# 32KRAM.net
KiCad netlist of a schematic drawn in EAGLE
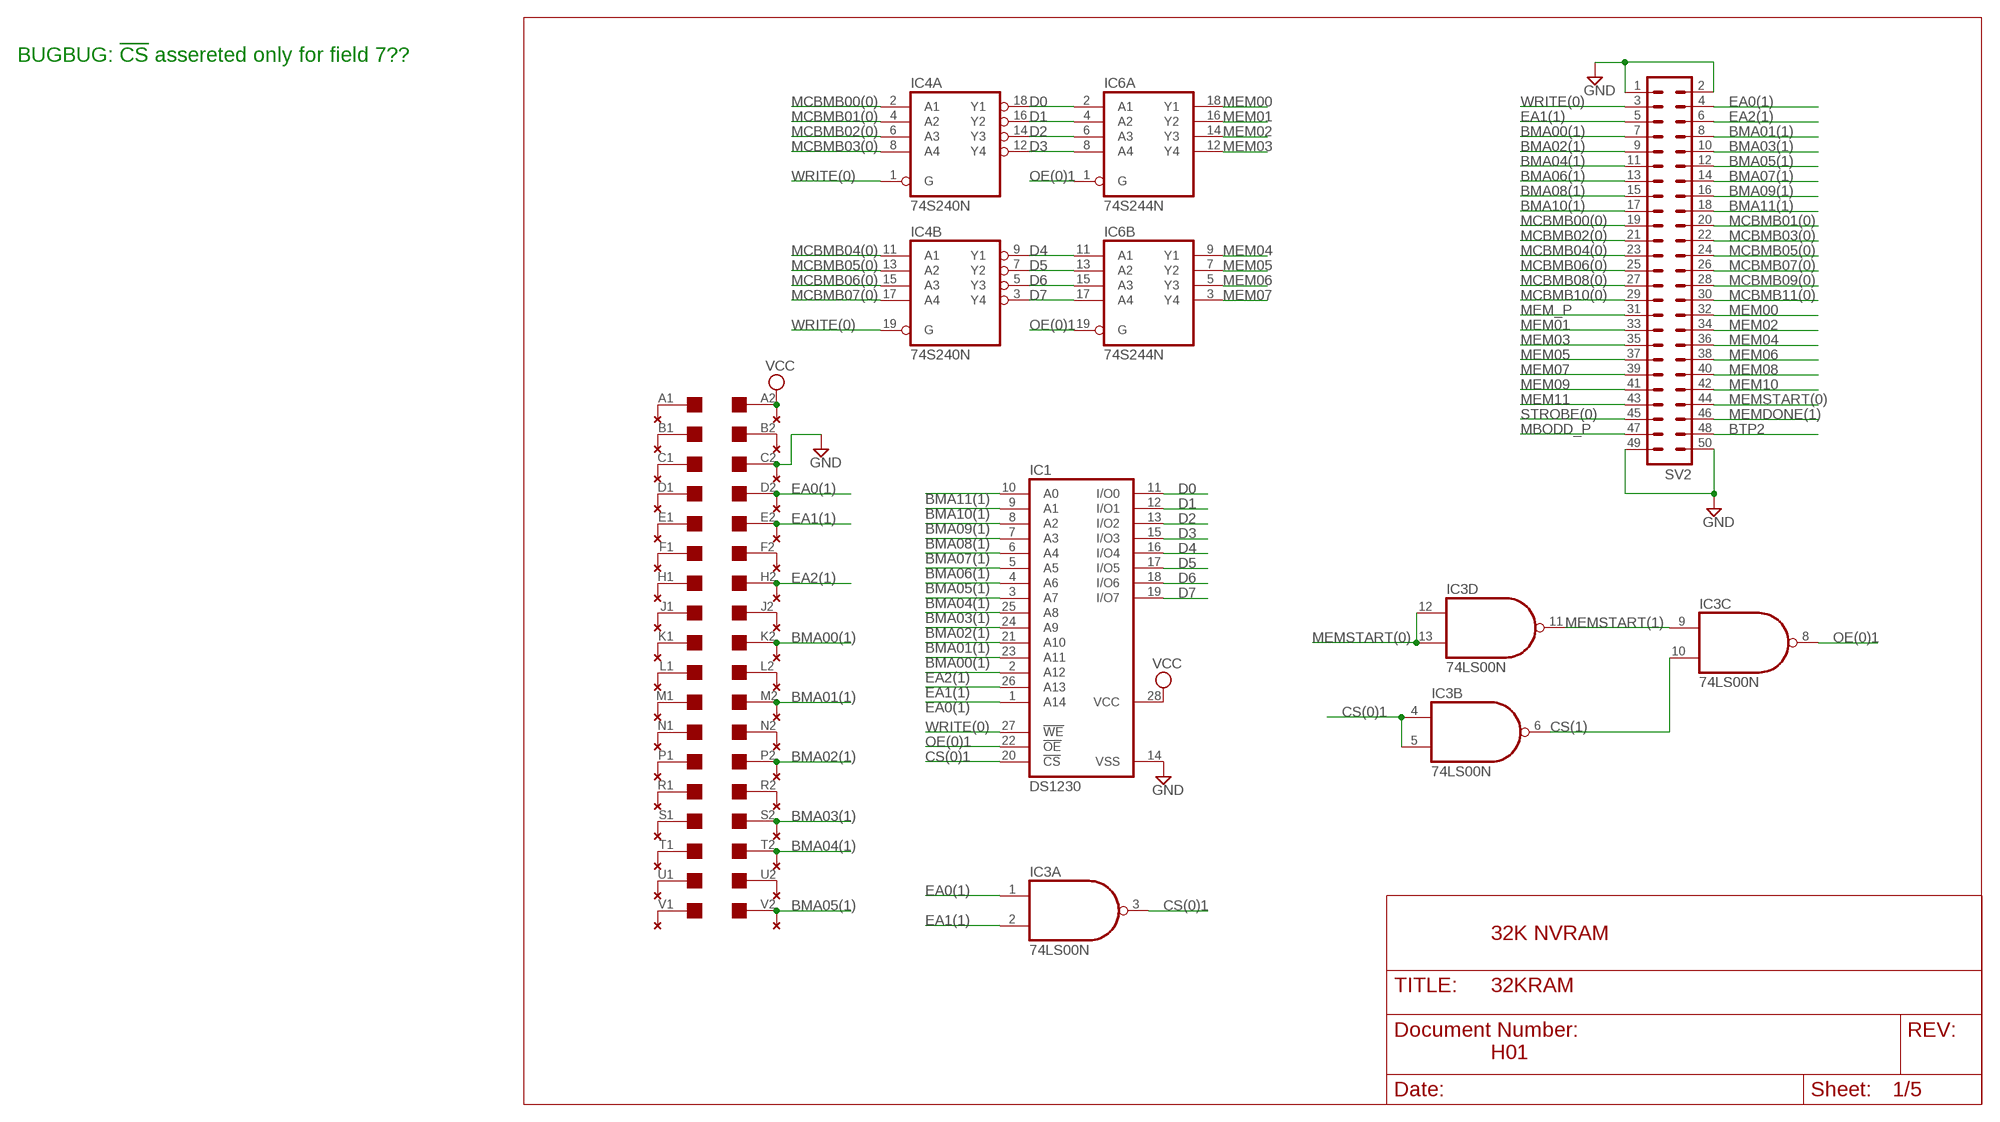
[diagram p0: schematic, sheet 1]
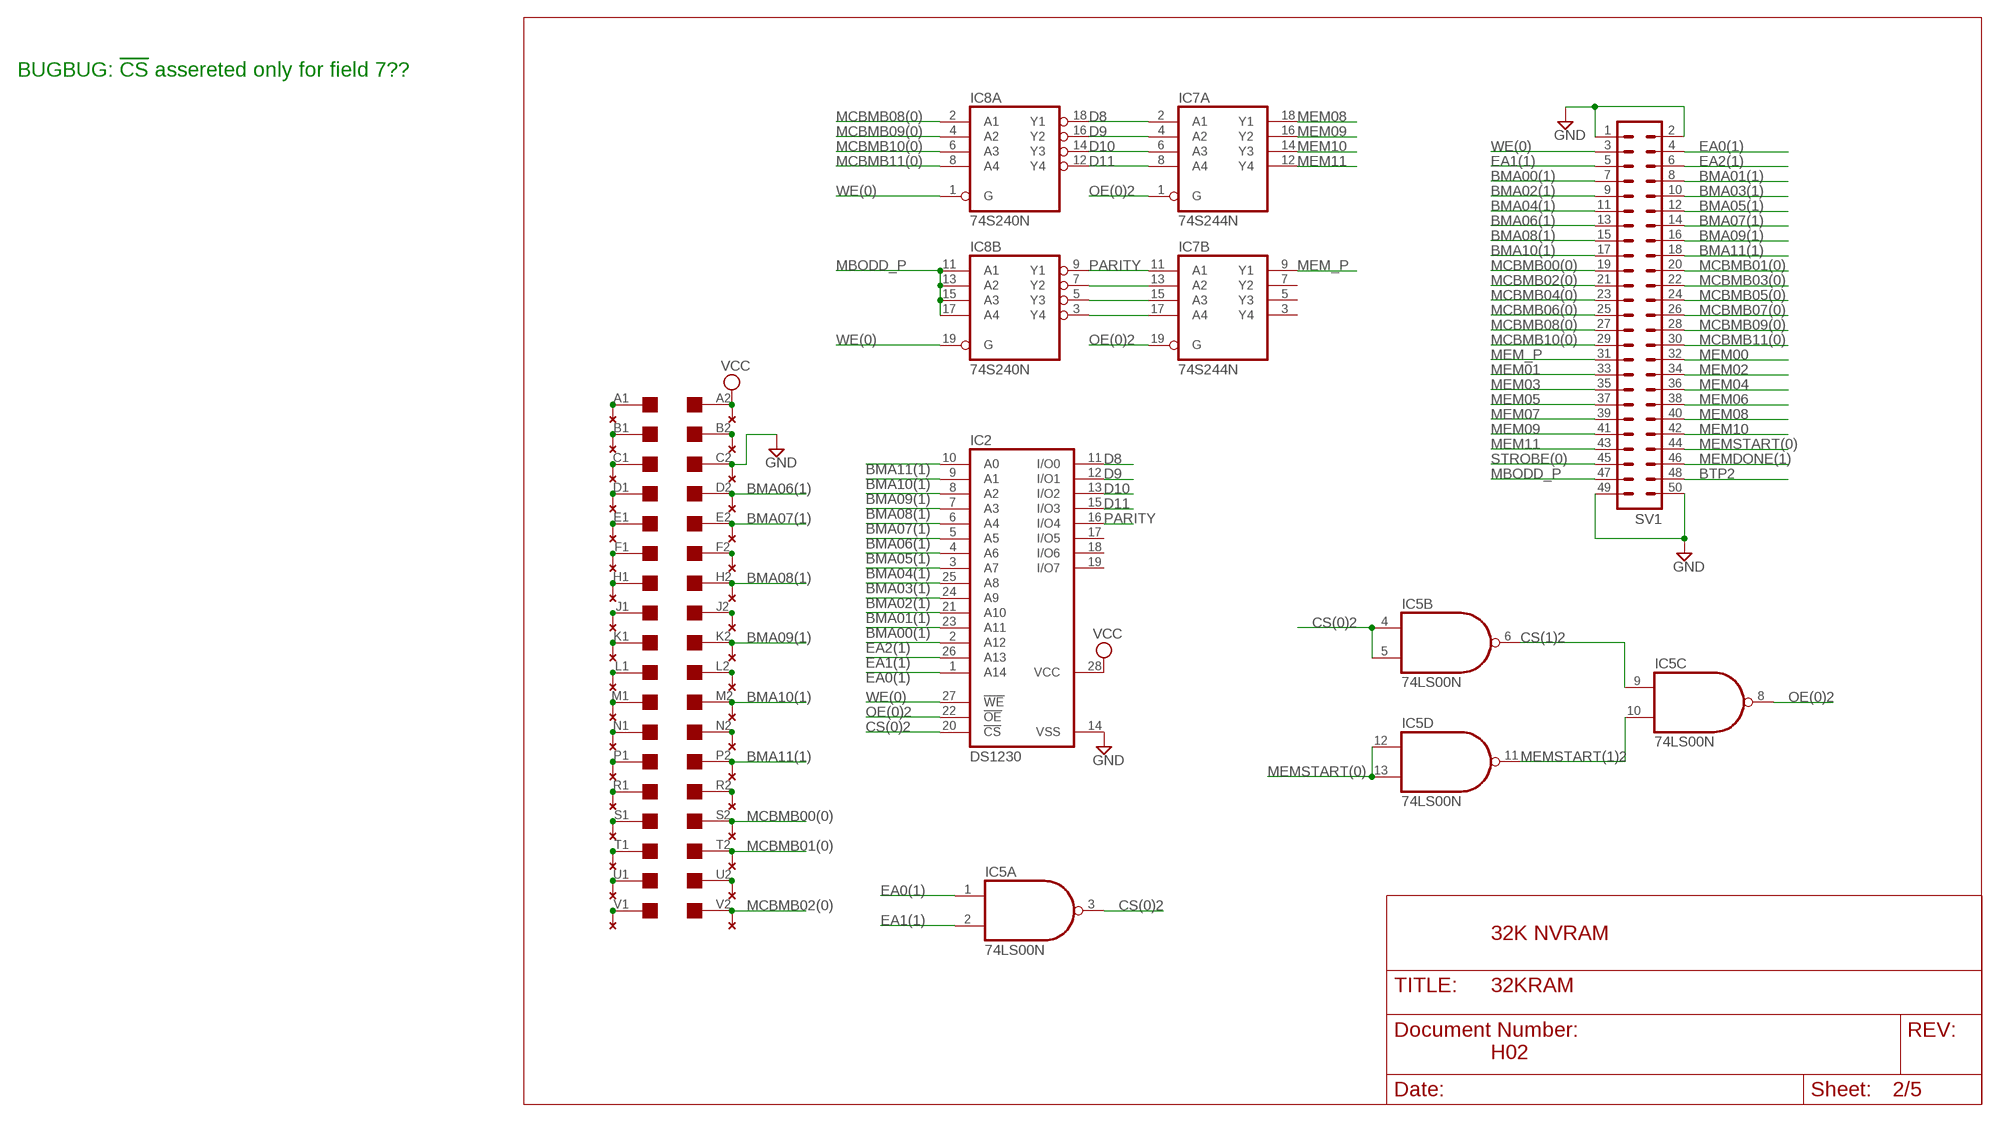
[diagram p1: schematic, sheet 2]
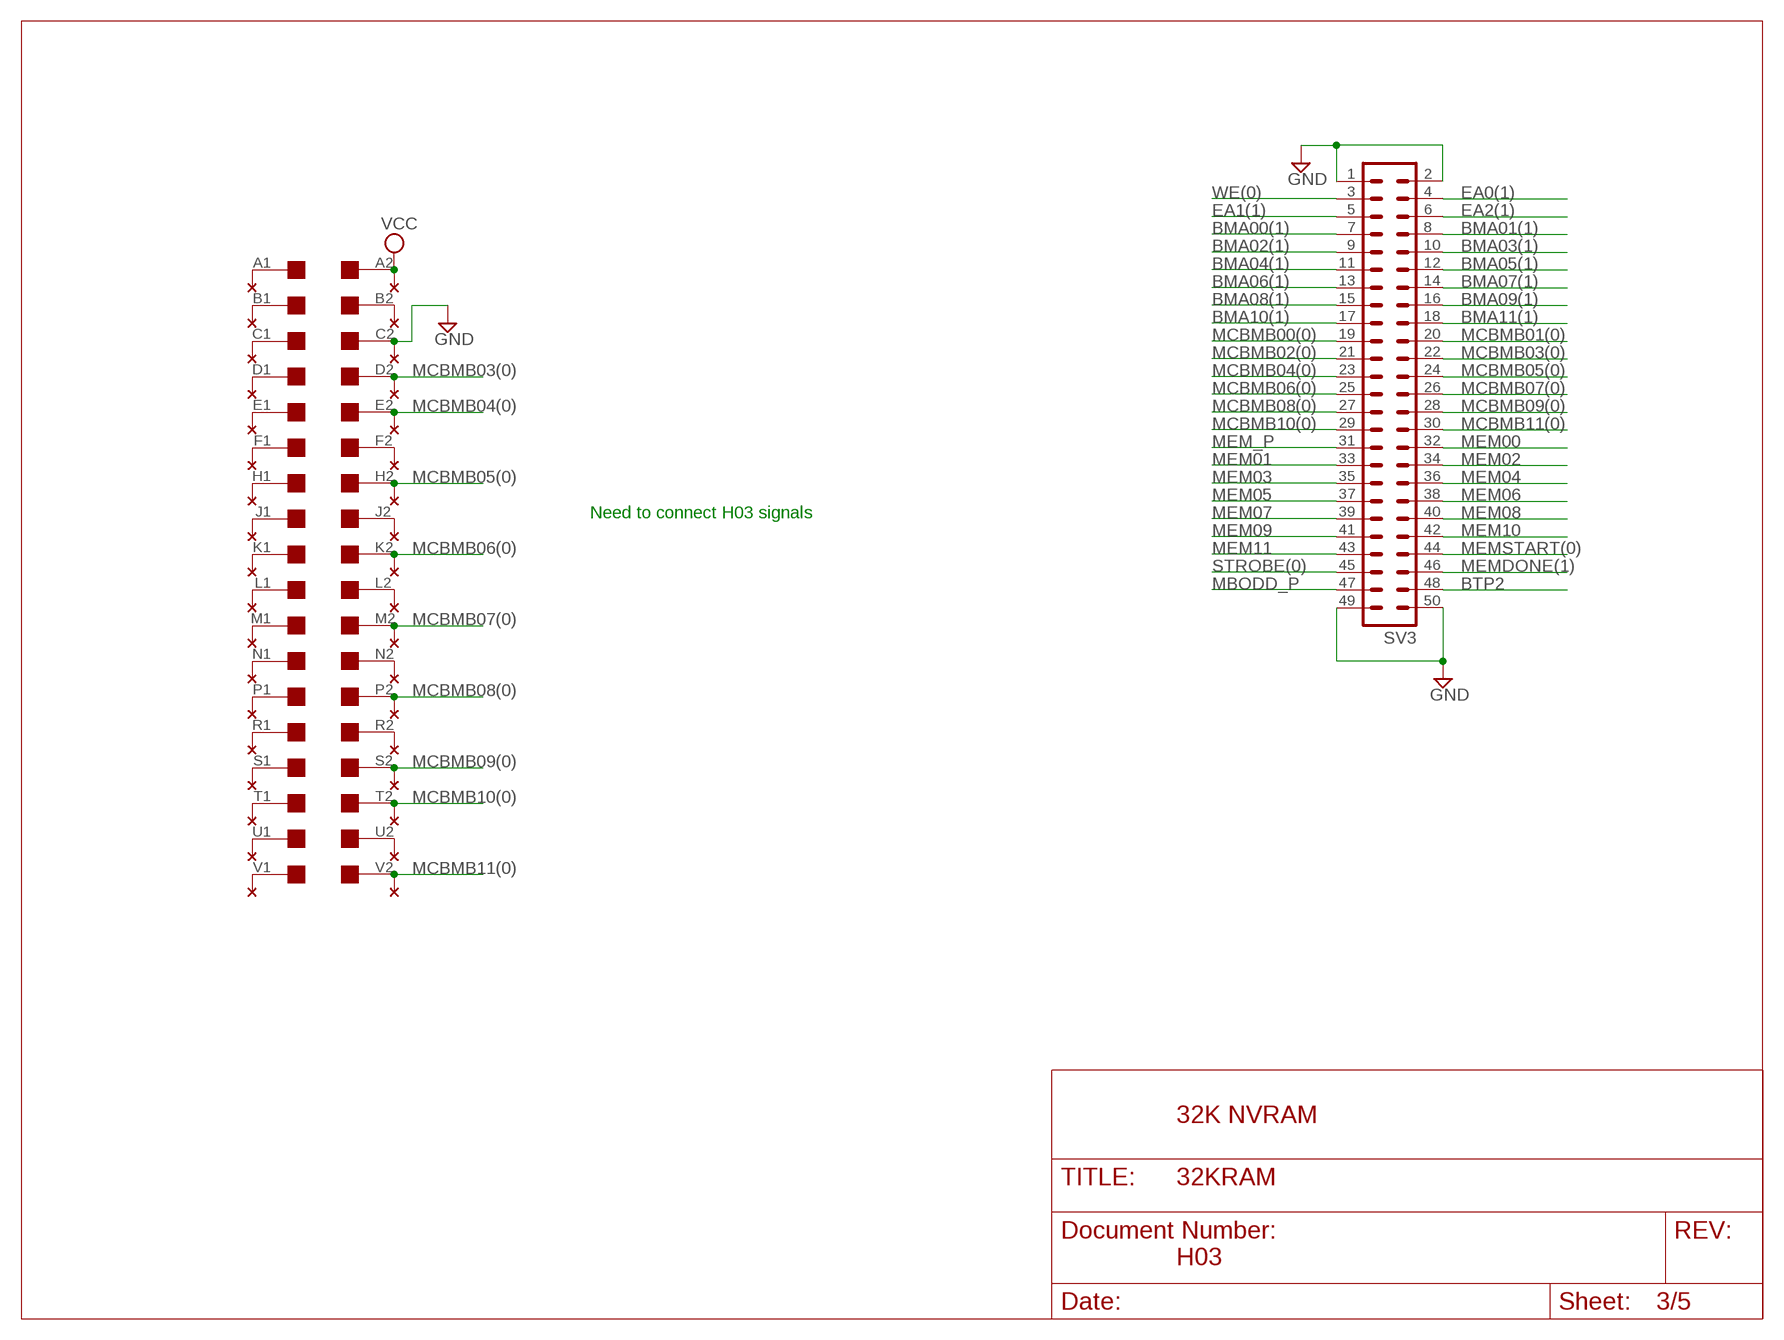
[diagram p2: schematic, sheet 3]
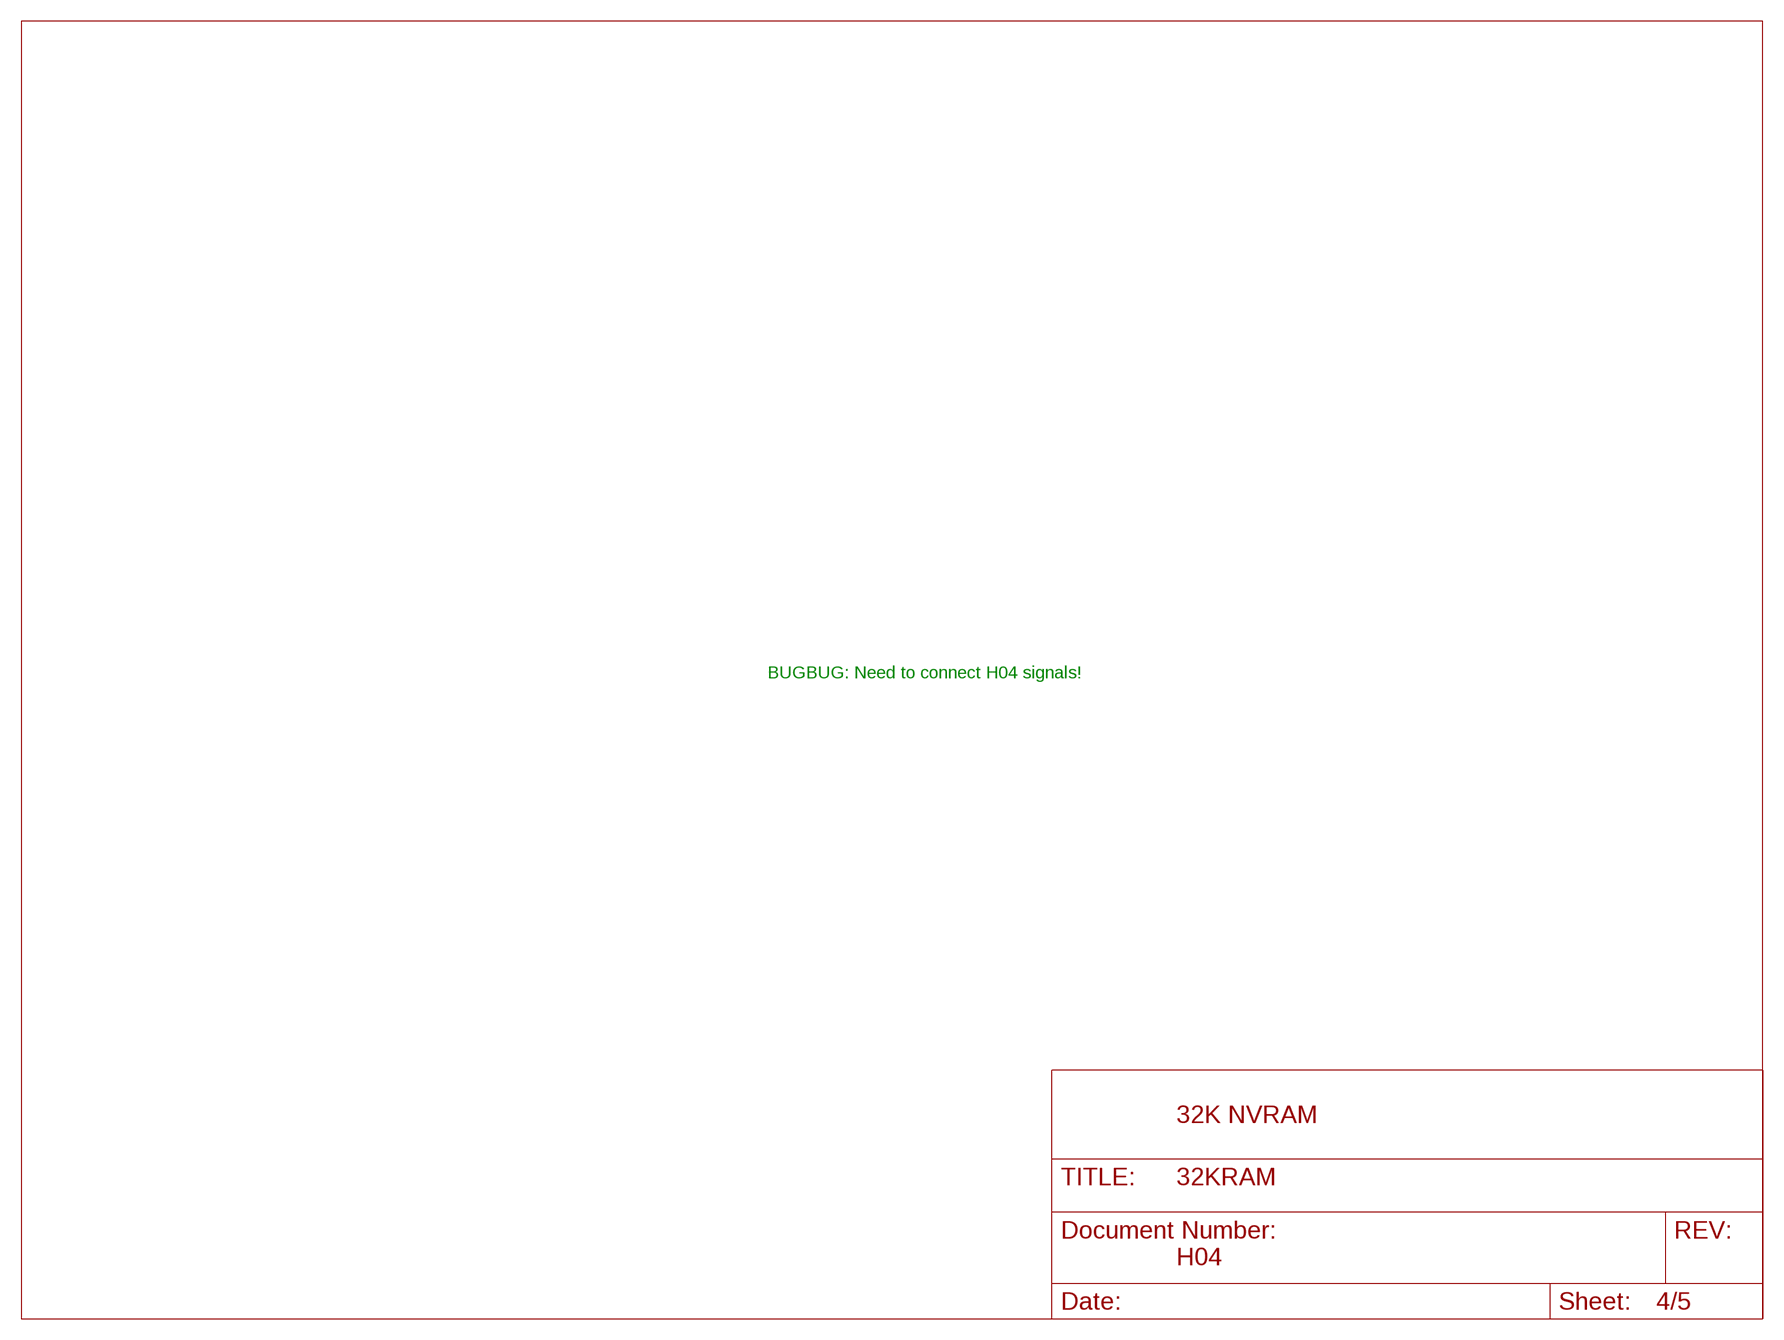
[diagram p3: schematic, sheet 4]
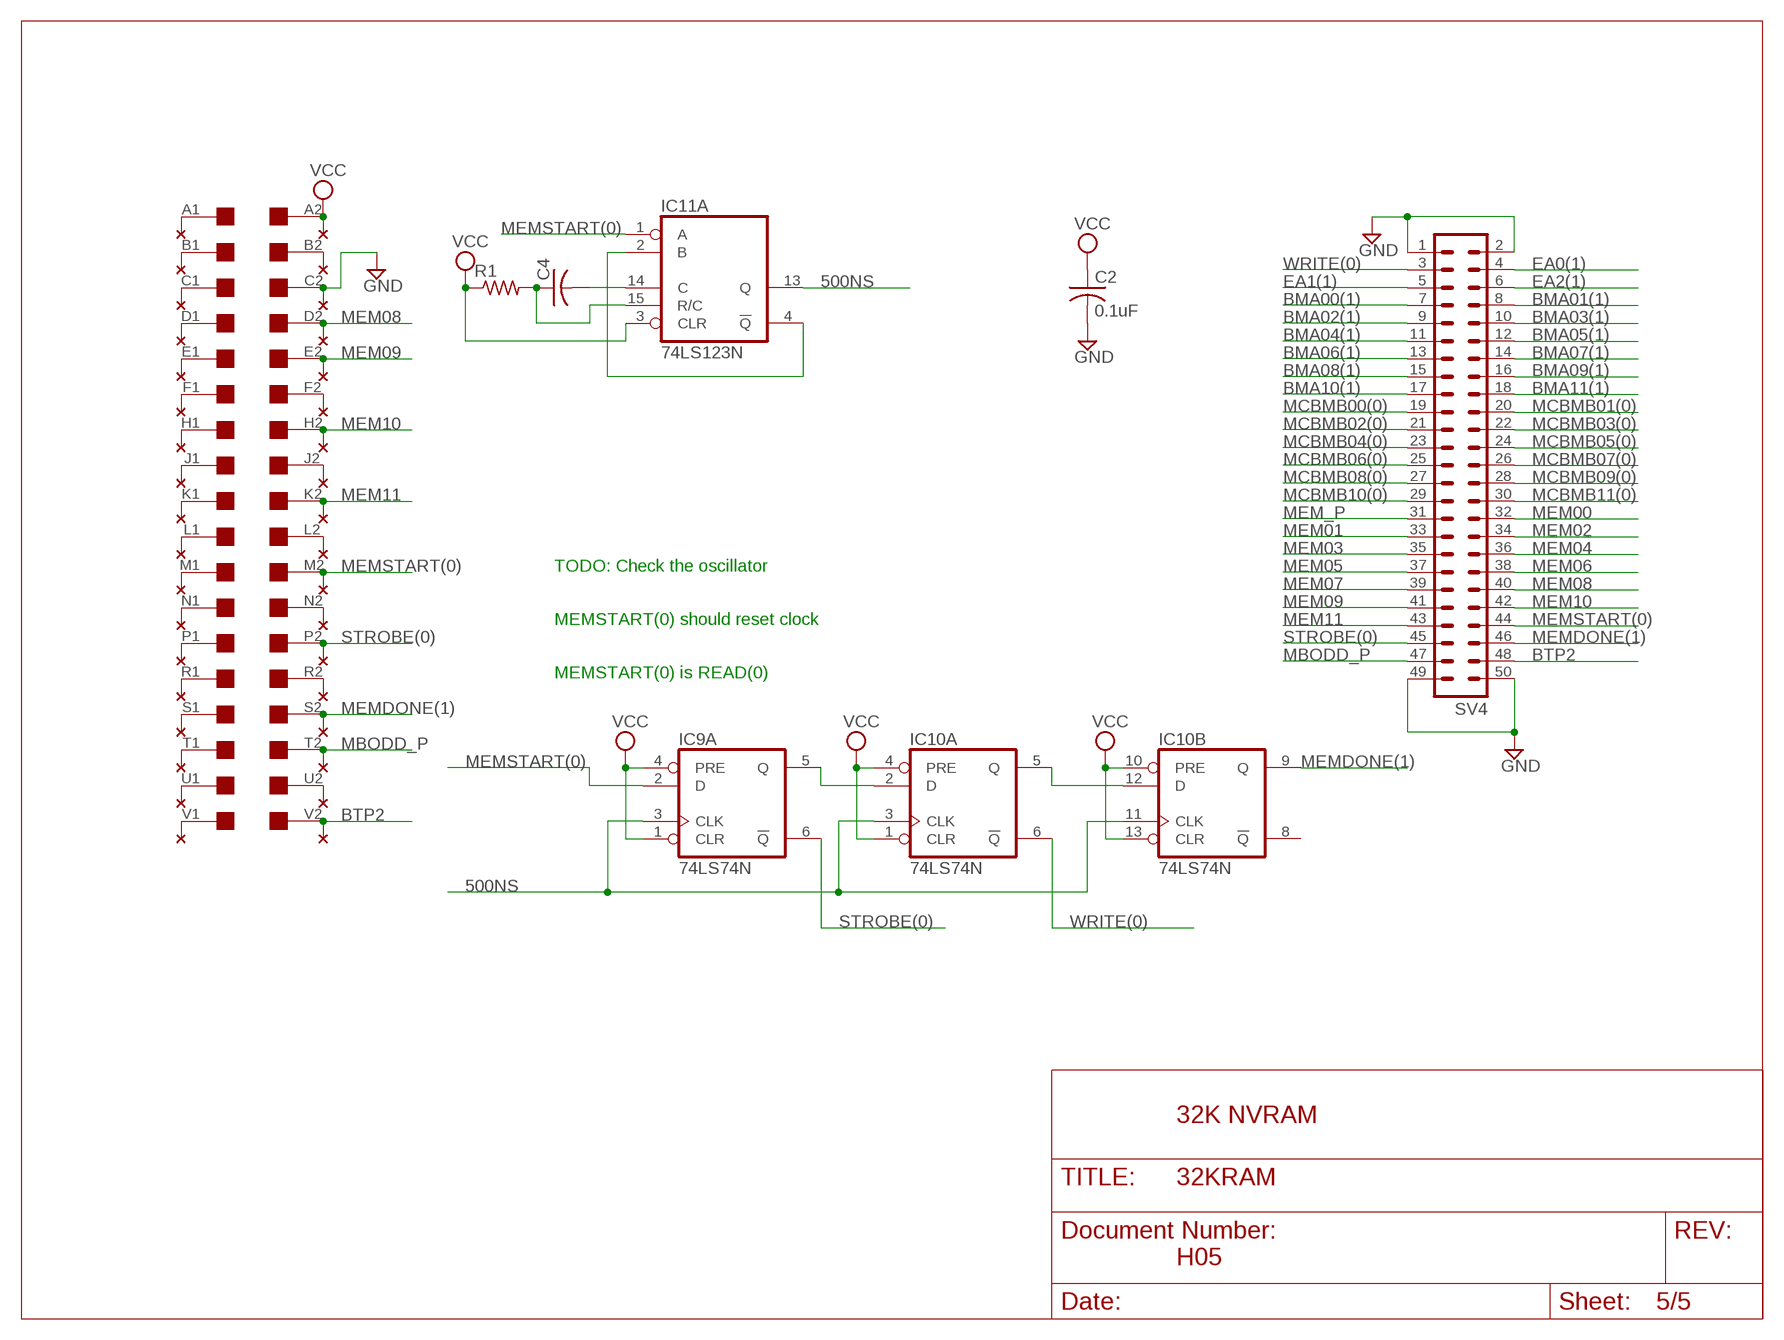
[diagram p4: schematic, sheet 5]

(export (version "E")
  (design (tool "Eeschema 10.0.6"))
  (components
    (comp (ref "EDGE3")
      (value "EDGE-2CONNECTOR")
      (footprint "eagle-import:EDGE-CON2")
      (libsource (lib "eagle-import") (part "EDGE-2CONNECTOR"))
    )
    (comp (ref "SV3")
      (value "ML50L")
      (footprint "eagle-import:ML50L")
      (libsource (lib "eagle-import") (part "ML50L"))
    )
    (comp (ref "U$3")
      (value "THRU-HOLE2")
      (footprint "eagle-import:THRU-HOLEB")
      (libsource (lib "eagle-import") (part "THRU-HOLE2"))
    )
    (comp (ref "EDGE1")
      (value "EDGE-2CONNECTOR")
      (footprint "eagle-import:EDGE-CON2")
      (libsource (lib "eagle-import") (part "EDGE-2CONNECTOR"))
    )
    (comp (ref "IC1")
      (value "DS1230")
      (footprint "eagle-import:DIL28-6")
      (libsource (lib "eagle-import") (part "62256P"))
    )
    (comp (ref "IC3")
      (value "74LS00N")
      (footprint "eagle-import:DIL14")
      (libsource (lib "eagle-import") (part "7400NLS"))
    )
    (comp (ref "IC4")
      (value "74S240N")
      (footprint "eagle-import:DIL20")
      (libsource (lib "eagle-import") (part "74240NS"))
    )
    (comp (ref "IC6")
      (value "74S244N")
      (footprint "eagle-import:DIL20")
      (libsource (lib "eagle-import") (part "74244NS"))
    )
    (comp (ref "SV2")
      (value "ML50L")
      (footprint "eagle-import:ML50L")
      (libsource (lib "eagle-import") (part "ML50L"))
    )
    (comp (ref "U$1")
      (value "THRU-HOLE2")
      (footprint "eagle-import:THRU-HOLEB")
      (libsource (lib "eagle-import") (part "THRU-HOLE2"))
    )
    (comp (ref "EDGE2")
      (value "EDGE-2CONNECTOR")
      (footprint "eagle-import:EDGE-CON2")
      (libsource (lib "eagle-import") (part "EDGE-2CONNECTOR"))
    )
    (comp (ref "IC2")
      (value "DS1230")
      (footprint "eagle-import:DIL28-6")
      (libsource (lib "eagle-import") (part "62256P"))
    )
    (comp (ref "IC5")
      (value "74LS00N")
      (footprint "eagle-import:DIL14")
      (libsource (lib "eagle-import") (part "7400NLS"))
    )
    (comp (ref "IC7")
      (value "74S244N")
      (footprint "eagle-import:DIL20")
      (libsource (lib "eagle-import") (part "74244NS"))
    )
    (comp (ref "IC8")
      (value "74S240N")
      (footprint "eagle-import:DIL20")
      (libsource (lib "eagle-import") (part "74240NS"))
    )
    (comp (ref "SV1")
      (value "ML50L")
      (footprint "eagle-import:ML50L")
      (libsource (lib "eagle-import") (part "ML50L"))
    )
    (comp (ref "U$2")
      (value "THRU-HOLE2")
      (footprint "eagle-import:THRU-HOLEB")
      (libsource (lib "eagle-import") (part "THRU-HOLE2"))
    )
    (comp (ref "C2")
      (value "0.1uF")
      (footprint "eagle-import:C050-025X075")
      (libsource (lib "eagle-import") (part "C-US050-025X075"))
    )
    (comp (ref "C4")
      (value "C-US050-025X075")
      (footprint "eagle-import:C050-025X075")
      (libsource (lib "eagle-import") (part "C-US050-025X075"))
    )
    (comp (ref "EDGE5")
      (value "EDGE-2CONNECTOR")
      (footprint "eagle-import:EDGE-CON2")
      (libsource (lib "eagle-import") (part "EDGE-2CONNECTOR"))
    )
    (comp (ref "IC9")
      (value "74LS74N")
      (footprint "eagle-import:DIL14")
      (libsource (lib "eagle-import") (part "7474NLS"))
    )
    (comp (ref "IC10")
      (value "74LS74N")
      (footprint "eagle-import:DIL14")
      (libsource (lib "eagle-import") (part "7474NLS"))
    )
    (comp (ref "IC11")
      (value "74LS123N")
      (footprint "eagle-import:DIL16")
      (libsource (lib "eagle-import") (part "74123NLS"))
    )
    (comp (ref "R1")
      (value "R-US_0309/10")
      (footprint "eagle-import:0309_10")
      (libsource (lib "eagle-import") (part "R-US_0309/10"))
    )
    (comp (ref "SV4")
      (value "ML50L")
      (footprint "eagle-import:ML50L")
      (libsource (lib "eagle-import") (part "ML50L"))
    )
    (comp (ref "U$5")
      (value "THRU-HOLE2")
      (footprint "eagle-import:THRU-HOLEB")
      (libsource (lib "eagle-import") (part "THRU-HOLE2"))
    )
  )
  (nets
    (net (code "1") (name "500NS") (class "Default")
      (node (ref "IC10") (pin "11") (pinfunction "CLK_11") (pintype "input"))
      (node (ref "IC10") (pin "3") (pinfunction "CLK_3") (pintype "input"))
      (node (ref "IC11") (pin "13") (pinfunction "Q_13") (pintype "output"))
      (node (ref "IC9") (pin "3") (pinfunction "CLK_3") (pintype "input"))
    )
    (net (code "2") (name "BMA00(1)") (class "Default")
      (node (ref "EDGE1") (pin "K2") (pinfunction "1_K2") (pintype "bidirectional"))
      (node (ref "IC1") (pin "23") (pinfunction "A11_23") (pintype "input"))
      (node (ref "IC2") (pin "23") (pinfunction "A11_23") (pintype "input"))
      (node (ref "SV1") (pin "7") (pinfunction "7_7") (pintype "passive"))
      (node (ref "SV2") (pin "7") (pinfunction "7_7") (pintype "passive"))
      (node (ref "SV3") (pin "7") (pinfunction "7_7") (pintype "passive"))
      (node (ref "SV4") (pin "7") (pinfunction "7_7") (pintype "passive"))
      (node (ref "U$1") (pin "K2") (pinfunction "P$1_K2") (pintype "passive"))
    )
    (net (code "3") (name "BMA01(1)") (class "Default")
      (node (ref "EDGE1") (pin "M2") (pinfunction "1_M2") (pintype "bidirectional"))
      (node (ref "IC1") (pin "21") (pinfunction "A10_21") (pintype "input"))
      (node (ref "IC2") (pin "21") (pinfunction "A10_21") (pintype "input"))
      (node (ref "SV1") (pin "8") (pinfunction "8_8") (pintype "passive"))
      (node (ref "SV2") (pin "8") (pinfunction "8_8") (pintype "passive"))
      (node (ref "SV3") (pin "8") (pinfunction "8_8") (pintype "passive"))
      (node (ref "SV4") (pin "8") (pinfunction "8_8") (pintype "passive"))
      (node (ref "U$1") (pin "M2") (pinfunction "P$1_M2") (pintype "passive"))
    )
    (net (code "4") (name "BMA02(1)") (class "Default")
      (node (ref "EDGE1") (pin "P2") (pinfunction "1_P2") (pintype "bidirectional"))
      (node (ref "IC1") (pin "24") (pinfunction "A9_24") (pintype "input"))
      (node (ref "IC2") (pin "24") (pinfunction "A9_24") (pintype "input"))
      (node (ref "SV1") (pin "9") (pinfunction "9_9") (pintype "passive"))
      (node (ref "SV2") (pin "9") (pinfunction "9_9") (pintype "passive"))
      (node (ref "SV3") (pin "9") (pinfunction "9_9") (pintype "passive"))
      (node (ref "SV4") (pin "9") (pinfunction "9_9") (pintype "passive"))
      (node (ref "U$1") (pin "P2") (pinfunction "P$1_P2") (pintype "passive"))
    )
    (net (code "5") (name "BMA03(1)") (class "Default")
      (node (ref "EDGE1") (pin "S2") (pinfunction "1_S2") (pintype "bidirectional"))
      (node (ref "IC1") (pin "25") (pinfunction "A8_25") (pintype "input"))
      (node (ref "IC2") (pin "25") (pinfunction "A8_25") (pintype "input"))
      (node (ref "SV1") (pin "10") (pinfunction "10_10") (pintype "passive"))
      (node (ref "SV2") (pin "10") (pinfunction "10_10") (pintype "passive"))
      (node (ref "SV3") (pin "10") (pinfunction "10_10") (pintype "passive"))
      (node (ref "SV4") (pin "10") (pinfunction "10_10") (pintype "passive"))
      (node (ref "U$1") (pin "S2") (pinfunction "P$1_S2") (pintype "passive"))
    )
    (net (code "6") (name "BMA04(1)") (class "Default")
      (node (ref "EDGE1") (pin "T2") (pinfunction "1_T2") (pintype "bidirectional"))
      (node (ref "IC1") (pin "3") (pinfunction "A7_3") (pintype "input"))
      (node (ref "IC2") (pin "3") (pinfunction "A7_3") (pintype "input"))
      (node (ref "SV1") (pin "11") (pinfunction "11_11") (pintype "passive"))
      (node (ref "SV2") (pin "11") (pinfunction "11_11") (pintype "passive"))
      (node (ref "SV3") (pin "11") (pinfunction "11_11") (pintype "passive"))
      (node (ref "SV4") (pin "11") (pinfunction "11_11") (pintype "passive"))
      (node (ref "U$1") (pin "T2") (pinfunction "P$1_T2") (pintype "passive"))
    )
    (net (code "7") (name "BMA05(1)") (class "Default")
      (node (ref "EDGE1") (pin "V2") (pinfunction "1_V2") (pintype "bidirectional"))
      (node (ref "IC1") (pin "4") (pinfunction "A6_4") (pintype "input"))
      (node (ref "IC2") (pin "4") (pinfunction "A6_4") (pintype "input"))
      (node (ref "SV1") (pin "12") (pinfunction "12_12") (pintype "passive"))
      (node (ref "SV2") (pin "12") (pinfunction "12_12") (pintype "passive"))
      (node (ref "SV3") (pin "12") (pinfunction "12_12") (pintype "passive"))
      (node (ref "SV4") (pin "12") (pinfunction "12_12") (pintype "passive"))
      (node (ref "U$1") (pin "V2") (pinfunction "P$1_V2") (pintype "passive"))
    )
    (net (code "8") (name "BMA06(1)") (class "Default")
      (node (ref "EDGE2") (pin "D2") (pinfunction "1_D2") (pintype "bidirectional"))
      (node (ref "IC1") (pin "5") (pinfunction "A5_5") (pintype "input"))
      (node (ref "IC2") (pin "5") (pinfunction "A5_5") (pintype "input"))
      (node (ref "SV1") (pin "13") (pinfunction "13_13") (pintype "passive"))
      (node (ref "SV2") (pin "13") (pinfunction "13_13") (pintype "passive"))
      (node (ref "SV3") (pin "13") (pinfunction "13_13") (pintype "passive"))
      (node (ref "SV4") (pin "13") (pinfunction "13_13") (pintype "passive"))
      (node (ref "U$2") (pin "D2") (pinfunction "P$1_D2") (pintype "passive"))
    )
    (net (code "9") (name "BMA07(1)") (class "Default")
      (node (ref "EDGE2") (pin "E2") (pinfunction "1_E2") (pintype "bidirectional"))
      (node (ref "IC1") (pin "6") (pinfunction "A4_6") (pintype "input"))
      (node (ref "IC2") (pin "6") (pinfunction "A4_6") (pintype "input"))
      (node (ref "SV1") (pin "14") (pinfunction "14_14") (pintype "passive"))
      (node (ref "SV2") (pin "14") (pinfunction "14_14") (pintype "passive"))
      (node (ref "SV3") (pin "14") (pinfunction "14_14") (pintype "passive"))
      (node (ref "SV4") (pin "14") (pinfunction "14_14") (pintype "passive"))
      (node (ref "U$2") (pin "E2") (pinfunction "P$1_E2") (pintype "passive"))
    )
    (net (code "10") (name "BMA08(1)") (class "Default")
      (node (ref "EDGE2") (pin "H2") (pinfunction "1_H2") (pintype "bidirectional"))
      (node (ref "IC1") (pin "7") (pinfunction "A3_7") (pintype "input"))
      (node (ref "IC2") (pin "7") (pinfunction "A3_7") (pintype "input"))
      (node (ref "SV1") (pin "15") (pinfunction "15_15") (pintype "passive"))
      (node (ref "SV2") (pin "15") (pinfunction "15_15") (pintype "passive"))
      (node (ref "SV3") (pin "15") (pinfunction "15_15") (pintype "passive"))
      (node (ref "SV4") (pin "15") (pinfunction "15_15") (pintype "passive"))
      (node (ref "U$2") (pin "H2") (pinfunction "P$1_H2") (pintype "passive"))
    )
    (net (code "11") (name "BMA09(1)") (class "Default")
      (node (ref "EDGE2") (pin "K2") (pinfunction "1_K2") (pintype "bidirectional"))
      (node (ref "IC1") (pin "8") (pinfunction "A2_8") (pintype "input"))
      (node (ref "IC2") (pin "8") (pinfunction "A2_8") (pintype "input"))
      (node (ref "SV1") (pin "16") (pinfunction "16_16") (pintype "passive"))
      (node (ref "SV2") (pin "16") (pinfunction "16_16") (pintype "passive"))
      (node (ref "SV3") (pin "16") (pinfunction "16_16") (pintype "passive"))
      (node (ref "SV4") (pin "16") (pinfunction "16_16") (pintype "passive"))
      (node (ref "U$2") (pin "K2") (pinfunction "P$1_K2") (pintype "passive"))
    )
    (net (code "12") (name "BMA10(1)") (class "Default")
      (node (ref "EDGE2") (pin "M2") (pinfunction "1_M2") (pintype "bidirectional"))
      (node (ref "IC1") (pin "9") (pinfunction "A1_9") (pintype "input"))
      (node (ref "IC2") (pin "9") (pinfunction "A1_9") (pintype "input"))
      (node (ref "SV1") (pin "17") (pinfunction "17_17") (pintype "passive"))
      (node (ref "SV2") (pin "17") (pinfunction "17_17") (pintype "passive"))
      (node (ref "SV3") (pin "17") (pinfunction "17_17") (pintype "passive"))
      (node (ref "SV4") (pin "17") (pinfunction "17_17") (pintype "passive"))
      (node (ref "U$2") (pin "M2") (pinfunction "P$1_M2") (pintype "passive"))
    )
    (net (code "13") (name "BMA11(1)") (class "Default")
      (node (ref "EDGE2") (pin "P2") (pinfunction "1_P2") (pintype "bidirectional"))
      (node (ref "IC1") (pin "10") (pinfunction "A0_10") (pintype "input"))
      (node (ref "IC2") (pin "10") (pinfunction "A0_10") (pintype "input"))
      (node (ref "SV1") (pin "18") (pinfunction "18_18") (pintype "passive"))
      (node (ref "SV2") (pin "18") (pinfunction "18_18") (pintype "passive"))
      (node (ref "SV3") (pin "18") (pinfunction "18_18") (pintype "passive"))
      (node (ref "SV4") (pin "18") (pinfunction "18_18") (pintype "passive"))
      (node (ref "U$2") (pin "P2") (pinfunction "P$1_P2") (pintype "passive"))
    )
    (net (code "14") (name "BTP2") (class "Default")
      (node (ref "EDGE5") (pin "V2") (pinfunction "1_V2") (pintype "bidirectional"))
      (node (ref "SV1") (pin "48") (pinfunction "48_48") (pintype "passive"))
      (node (ref "SV2") (pin "48") (pinfunction "48_48") (pintype "passive"))
      (node (ref "SV3") (pin "48") (pinfunction "48_48") (pintype "passive"))
      (node (ref "SV4") (pin "48") (pinfunction "48_48") (pintype "passive"))
      (node (ref "U$5") (pin "V2") (pinfunction "P$1_V2") (pintype "passive"))
    )
    (net (code "15") (name "CS(0)1") (class "Default")
      (node (ref "IC1") (pin "20") (pinfunction "~{CS}_20") (pintype "input"))
      (node (ref "IC3") (pin "3") (pinfunction "O_3") (pintype "output"))
      (node (ref "IC3") (pin "4") (pinfunction "I0_4") (pintype "input"))
      (node (ref "IC3") (pin "5") (pinfunction "I1_5") (pintype "input"))
    )
    (net (code "16") (name "CS(0)2") (class "Default")
      (node (ref "IC2") (pin "20") (pinfunction "~{CS}_20") (pintype "input"))
      (node (ref "IC5") (pin "3") (pinfunction "O_3") (pintype "output"))
      (node (ref "IC5") (pin "4") (pinfunction "I0_4") (pintype "input"))
      (node (ref "IC5") (pin "5") (pinfunction "I1_5") (pintype "input"))
    )
    (net (code "17") (name "CS(1)") (class "Default")
      (node (ref "IC3") (pin "10") (pinfunction "I1_10") (pintype "input"))
      (node (ref "IC3") (pin "6") (pinfunction "O_6") (pintype "output"))
    )
    (net (code "18") (name "CS(1)2") (class "Default")
      (node (ref "IC5") (pin "6") (pinfunction "O_6") (pintype "output"))
      (node (ref "IC5") (pin "9") (pinfunction "I0_9") (pintype "input"))
    )
    (net (code "19") (name "D0") (class "Default")
      (node (ref "IC1") (pin "11") (pinfunction "I/O0_11") (pintype "bidirectional"))
      (node (ref "IC4") (pin "18") (pinfunction "Y1_18") (pintype "tri_state"))
      (node (ref "IC6") (pin "2") (pinfunction "A1_2") (pintype "input"))
    )
    (net (code "20") (name "D1") (class "Default")
      (node (ref "IC1") (pin "12") (pinfunction "I/O1_12") (pintype "bidirectional"))
      (node (ref "IC4") (pin "16") (pinfunction "Y2_16") (pintype "tri_state"))
      (node (ref "IC6") (pin "4") (pinfunction "A2_4") (pintype "input"))
    )
    (net (code "21") (name "D2") (class "Default")
      (node (ref "IC1") (pin "13") (pinfunction "I/O2_13") (pintype "bidirectional"))
      (node (ref "IC4") (pin "14") (pinfunction "Y3_14") (pintype "tri_state"))
      (node (ref "IC6") (pin "6") (pinfunction "A3_6") (pintype "input"))
    )
    (net (code "22") (name "D3") (class "Default")
      (node (ref "IC1") (pin "15") (pinfunction "I/O3_15") (pintype "bidirectional"))
      (node (ref "IC4") (pin "12") (pinfunction "Y4_12") (pintype "tri_state"))
      (node (ref "IC6") (pin "8") (pinfunction "A4_8") (pintype "input"))
    )
    (net (code "23") (name "D4") (class "Default")
      (node (ref "IC1") (pin "16") (pinfunction "I/O4_16") (pintype "bidirectional"))
      (node (ref "IC4") (pin "9") (pinfunction "Y1_9") (pintype "tri_state"))
      (node (ref "IC6") (pin "11") (pinfunction "A1_11") (pintype "input"))
    )
    (net (code "24") (name "D5") (class "Default")
      (node (ref "IC1") (pin "17") (pinfunction "I/O5_17") (pintype "bidirectional"))
      (node (ref "IC4") (pin "7") (pinfunction "Y2_7") (pintype "tri_state"))
      (node (ref "IC6") (pin "13") (pinfunction "A2_13") (pintype "input"))
    )
    (net (code "25") (name "D6") (class "Default")
      (node (ref "IC1") (pin "18") (pinfunction "I/O6_18") (pintype "bidirectional"))
      (node (ref "IC4") (pin "5") (pinfunction "Y3_5") (pintype "tri_state"))
      (node (ref "IC6") (pin "15") (pinfunction "A3_15") (pintype "input"))
    )
    (net (code "26") (name "D7") (class "Default")
      (node (ref "IC1") (pin "19") (pinfunction "I/O7_19") (pintype "bidirectional"))
      (node (ref "IC4") (pin "3") (pinfunction "Y4_3") (pintype "tri_state"))
      (node (ref "IC6") (pin "17") (pinfunction "A4_17") (pintype "input"))
    )
    (net (code "27") (name "D8") (class "Default")
      (node (ref "IC2") (pin "11") (pinfunction "I/O0_11") (pintype "bidirectional"))
      (node (ref "IC7") (pin "2") (pinfunction "A1_2") (pintype "input"))
      (node (ref "IC8") (pin "18") (pinfunction "Y1_18") (pintype "tri_state"))
    )
    (net (code "28") (name "D9") (class "Default")
      (node (ref "IC2") (pin "12") (pinfunction "I/O1_12") (pintype "bidirectional"))
      (node (ref "IC7") (pin "4") (pinfunction "A2_4") (pintype "input"))
      (node (ref "IC8") (pin "16") (pinfunction "Y2_16") (pintype "tri_state"))
    )
    (net (code "29") (name "D10") (class "Default")
      (node (ref "IC2") (pin "13") (pinfunction "I/O2_13") (pintype "bidirectional"))
      (node (ref "IC7") (pin "6") (pinfunction "A3_6") (pintype "input"))
      (node (ref "IC8") (pin "14") (pinfunction "Y3_14") (pintype "tri_state"))
    )
    (net (code "30") (name "D11") (class "Default")
      (node (ref "IC2") (pin "15") (pinfunction "I/O3_15") (pintype "bidirectional"))
      (node (ref "IC7") (pin "8") (pinfunction "A4_8") (pintype "input"))
      (node (ref "IC8") (pin "12") (pinfunction "Y4_12") (pintype "tri_state"))
    )
    (net (code "31") (name "EA0(1)") (class "Default")
      (node (ref "EDGE1") (pin "D2") (pinfunction "1_D2") (pintype "bidirectional"))
      (node (ref "IC1") (pin "1") (pinfunction "A14_1") (pintype "input"))
      (node (ref "IC2") (pin "1") (pinfunction "A14_1") (pintype "input"))
      (node (ref "IC3") (pin "1") (pinfunction "I0_1") (pintype "input"))
      (node (ref "IC5") (pin "1") (pinfunction "I0_1") (pintype "input"))
      (node (ref "SV1") (pin "4") (pinfunction "4_4") (pintype "passive"))
      (node (ref "SV2") (pin "4") (pinfunction "4_4") (pintype "passive"))
      (node (ref "SV3") (pin "4") (pinfunction "4_4") (pintype "passive"))
      (node (ref "SV4") (pin "4") (pinfunction "4_4") (pintype "passive"))
      (node (ref "U$1") (pin "D2") (pinfunction "P$1_D2") (pintype "passive"))
    )
    (net (code "32") (name "EA1(1)") (class "Default")
      (node (ref "EDGE1") (pin "E2") (pinfunction "1_E2") (pintype "bidirectional"))
      (node (ref "IC1") (pin "26") (pinfunction "A13_26") (pintype "input"))
      (node (ref "IC2") (pin "26") (pinfunction "A13_26") (pintype "input"))
      (node (ref "IC3") (pin "2") (pinfunction "I1_2") (pintype "input"))
      (node (ref "IC5") (pin "2") (pinfunction "I1_2") (pintype "input"))
      (node (ref "SV1") (pin "5") (pinfunction "5_5") (pintype "passive"))
      (node (ref "SV2") (pin "5") (pinfunction "5_5") (pintype "passive"))
      (node (ref "SV3") (pin "5") (pinfunction "5_5") (pintype "passive"))
      (node (ref "SV4") (pin "5") (pinfunction "5_5") (pintype "passive"))
      (node (ref "U$1") (pin "E2") (pinfunction "P$1_E2") (pintype "passive"))
    )
    (net (code "33") (name "EA2(1)") (class "Default")
      (node (ref "EDGE1") (pin "H2") (pinfunction "1_H2") (pintype "bidirectional"))
      (node (ref "IC1") (pin "2") (pinfunction "A12_2") (pintype "input"))
      (node (ref "IC2") (pin "2") (pinfunction "A12_2") (pintype "input"))
      (node (ref "SV1") (pin "6") (pinfunction "6_6") (pintype "passive"))
      (node (ref "SV2") (pin "6") (pinfunction "6_6") (pintype "passive"))
      (node (ref "SV3") (pin "6") (pinfunction "6_6") (pintype "passive"))
      (node (ref "SV4") (pin "6") (pinfunction "6_6") (pintype "passive"))
      (node (ref "U$1") (pin "H2") (pinfunction "P$1_H2") (pintype "passive"))
    )
    (net (code "34") (name "GND") (class "Default")
      (node (ref "C2") (pin "2") (pinfunction "2_2") (pintype "passive"))
      (node (ref "EDGE1") (pin "C2") (pinfunction "1_C2") (pintype "bidirectional"))
      (node (ref "EDGE2") (pin "C2") (pinfunction "1_C2") (pintype "bidirectional"))
      (node (ref "EDGE3") (pin "C2") (pinfunction "1_C2") (pintype "bidirectional"))
      (node (ref "EDGE5") (pin "C2") (pinfunction "1_C2") (pintype "bidirectional"))
      (node (ref "IC1") (pin "14") (pinfunction "VSS_14") (pintype "power_in"))
      (node (ref "IC2") (pin "14") (pinfunction "VSS_14") (pintype "power_in"))
      (node (ref "SV1") (pin "1") (pinfunction "1_1") (pintype "passive"))
      (node (ref "SV1") (pin "2") (pinfunction "2_2") (pintype "passive"))
      (node (ref "SV1") (pin "49") (pinfunction "49_49") (pintype "passive"))
      (node (ref "SV1") (pin "50") (pinfunction "50_50") (pintype "passive"))
      (node (ref "SV2") (pin "1") (pinfunction "1_1") (pintype "passive"))
      (node (ref "SV2") (pin "2") (pinfunction "2_2") (pintype "passive"))
      (node (ref "SV2") (pin "49") (pinfunction "49_49") (pintype "passive"))
      (node (ref "SV2") (pin "50") (pinfunction "50_50") (pintype "passive"))
      (node (ref "SV3") (pin "1") (pinfunction "1_1") (pintype "passive"))
      (node (ref "SV3") (pin "2") (pinfunction "2_2") (pintype "passive"))
      (node (ref "SV3") (pin "49") (pinfunction "49_49") (pintype "passive"))
      (node (ref "SV3") (pin "50") (pinfunction "50_50") (pintype "passive"))
      (node (ref "SV4") (pin "1") (pinfunction "1_1") (pintype "passive"))
      (node (ref "SV4") (pin "2") (pinfunction "2_2") (pintype "passive"))
      (node (ref "SV4") (pin "49") (pinfunction "49_49") (pintype "passive"))
      (node (ref "SV4") (pin "50") (pinfunction "50_50") (pintype "passive"))
      (node (ref "U$1") (pin "C2") (pinfunction "P$1_C2") (pintype "passive"))
      (node (ref "U$2") (pin "C2") (pinfunction "P$1_C2") (pintype "passive"))
      (node (ref "U$3") (pin "C2") (pinfunction "P$1_C2") (pintype "passive"))
      (node (ref "U$5") (pin "C2") (pinfunction "P$1_C2") (pintype "passive"))
    )
    (net (code "35") (name "MBODD_P") (class "Default")
      (node (ref "EDGE5") (pin "T2") (pinfunction "1_T2") (pintype "bidirectional"))
      (node (ref "IC8") (pin "11") (pinfunction "A1_11") (pintype "input"))
      (node (ref "IC8") (pin "13") (pinfunction "A2_13") (pintype "input"))
      (node (ref "IC8") (pin "15") (pinfunction "A3_15") (pintype "input"))
      (node (ref "IC8") (pin "17") (pinfunction "A4_17") (pintype "input"))
      (node (ref "SV1") (pin "47") (pinfunction "47_47") (pintype "passive"))
      (node (ref "SV2") (pin "47") (pinfunction "47_47") (pintype "passive"))
      (node (ref "SV3") (pin "47") (pinfunction "47_47") (pintype "passive"))
      (node (ref "SV4") (pin "47") (pinfunction "47_47") (pintype "passive"))
      (node (ref "U$5") (pin "T2") (pinfunction "P$1_T2") (pintype "passive"))
    )
    (net (code "36") (name "MCBMB00(0)") (class "Default")
      (node (ref "EDGE2") (pin "S2") (pinfunction "1_S2") (pintype "bidirectional"))
      (node (ref "IC4") (pin "2") (pinfunction "A1_2") (pintype "input"))
      (node (ref "SV1") (pin "19") (pinfunction "19_19") (pintype "passive"))
      (node (ref "SV2") (pin "19") (pinfunction "19_19") (pintype "passive"))
      (node (ref "SV3") (pin "19") (pinfunction "19_19") (pintype "passive"))
      (node (ref "SV4") (pin "19") (pinfunction "19_19") (pintype "passive"))
      (node (ref "U$2") (pin "S2") (pinfunction "P$1_S2") (pintype "passive"))
    )
    (net (code "37") (name "MCBMB01(0)") (class "Default")
      (node (ref "EDGE2") (pin "T2") (pinfunction "1_T2") (pintype "bidirectional"))
      (node (ref "IC4") (pin "4") (pinfunction "A2_4") (pintype "input"))
      (node (ref "SV1") (pin "20") (pinfunction "20_20") (pintype "passive"))
      (node (ref "SV2") (pin "20") (pinfunction "20_20") (pintype "passive"))
      (node (ref "SV3") (pin "20") (pinfunction "20_20") (pintype "passive"))
      (node (ref "SV4") (pin "20") (pinfunction "20_20") (pintype "passive"))
      (node (ref "U$2") (pin "T2") (pinfunction "P$1_T2") (pintype "passive"))
    )
    (net (code "38") (name "MCBMB02(0)") (class "Default")
      (node (ref "EDGE2") (pin "V2") (pinfunction "1_V2") (pintype "bidirectional"))
      (node (ref "IC4") (pin "6") (pinfunction "A3_6") (pintype "input"))
      (node (ref "SV1") (pin "21") (pinfunction "21_21") (pintype "passive"))
      (node (ref "SV2") (pin "21") (pinfunction "21_21") (pintype "passive"))
      (node (ref "SV3") (pin "21") (pinfunction "21_21") (pintype "passive"))
      (node (ref "SV4") (pin "21") (pinfunction "21_21") (pintype "passive"))
      (node (ref "U$2") (pin "V2") (pinfunction "P$1_V2") (pintype "passive"))
    )
    (net (code "39") (name "MCBMB03(0)") (class "Default")
      (node (ref "EDGE3") (pin "D2") (pinfunction "1_D2") (pintype "bidirectional"))
      (node (ref "IC4") (pin "8") (pinfunction "A4_8") (pintype "input"))
      (node (ref "SV1") (pin "22") (pinfunction "22_22") (pintype "passive"))
      (node (ref "SV2") (pin "22") (pinfunction "22_22") (pintype "passive"))
      (node (ref "SV3") (pin "22") (pinfunction "22_22") (pintype "passive"))
      (node (ref "SV4") (pin "22") (pinfunction "22_22") (pintype "passive"))
      (node (ref "U$3") (pin "D2") (pinfunction "P$1_D2") (pintype "passive"))
    )
    (net (code "40") (name "MCBMB04(0)") (class "Default")
      (node (ref "EDGE3") (pin "E2") (pinfunction "1_E2") (pintype "bidirectional"))
      (node (ref "IC4") (pin "11") (pinfunction "A1_11") (pintype "input"))
      (node (ref "SV1") (pin "23") (pinfunction "23_23") (pintype "passive"))
      (node (ref "SV2") (pin "23") (pinfunction "23_23") (pintype "passive"))
      (node (ref "SV3") (pin "23") (pinfunction "23_23") (pintype "passive"))
      (node (ref "SV4") (pin "23") (pinfunction "23_23") (pintype "passive"))
      (node (ref "U$3") (pin "E2") (pinfunction "P$1_E2") (pintype "passive"))
    )
    (net (code "41") (name "MCBMB05(0)") (class "Default")
      (node (ref "EDGE3") (pin "H2") (pinfunction "1_H2") (pintype "bidirectional"))
      (node (ref "IC4") (pin "13") (pinfunction "A2_13") (pintype "input"))
      (node (ref "SV1") (pin "24") (pinfunction "24_24") (pintype "passive"))
      (node (ref "SV2") (pin "24") (pinfunction "24_24") (pintype "passive"))
      (node (ref "SV3") (pin "24") (pinfunction "24_24") (pintype "passive"))
      (node (ref "SV4") (pin "24") (pinfunction "24_24") (pintype "passive"))
      (node (ref "U$3") (pin "H2") (pinfunction "P$1_H2") (pintype "passive"))
    )
    (net (code "42") (name "MCBMB06(0)") (class "Default")
      (node (ref "EDGE3") (pin "K2") (pinfunction "1_K2") (pintype "bidirectional"))
      (node (ref "IC4") (pin "15") (pinfunction "A3_15") (pintype "input"))
      (node (ref "SV1") (pin "25") (pinfunction "25_25") (pintype "passive"))
      (node (ref "SV2") (pin "25") (pinfunction "25_25") (pintype "passive"))
      (node (ref "SV3") (pin "25") (pinfunction "25_25") (pintype "passive"))
      (node (ref "SV4") (pin "25") (pinfunction "25_25") (pintype "passive"))
      (node (ref "U$3") (pin "K2") (pinfunction "P$1_K2") (pintype "passive"))
    )
    (net (code "43") (name "MCBMB07(0)") (class "Default")
      (node (ref "EDGE3") (pin "M2") (pinfunction "1_M2") (pintype "bidirectional"))
      (node (ref "IC4") (pin "17") (pinfunction "A4_17") (pintype "input"))
      (node (ref "SV1") (pin "26") (pinfunction "26_26") (pintype "passive"))
      (node (ref "SV2") (pin "26") (pinfunction "26_26") (pintype "passive"))
      (node (ref "SV3") (pin "26") (pinfunction "26_26") (pintype "passive"))
      (node (ref "SV4") (pin "26") (pinfunction "26_26") (pintype "passive"))
      (node (ref "U$3") (pin "M2") (pinfunction "P$1_M2") (pintype "passive"))
    )
    (net (code "44") (name "MCBMB08(0)") (class "Default")
      (node (ref "EDGE3") (pin "P2") (pinfunction "1_P2") (pintype "bidirectional"))
      (node (ref "IC8") (pin "2") (pinfunction "A1_2") (pintype "input"))
      (node (ref "SV1") (pin "27") (pinfunction "27_27") (pintype "passive"))
      (node (ref "SV2") (pin "27") (pinfunction "27_27") (pintype "passive"))
      (node (ref "SV3") (pin "27") (pinfunction "27_27") (pintype "passive"))
      (node (ref "SV4") (pin "27") (pinfunction "27_27") (pintype "passive"))
      (node (ref "U$3") (pin "P2") (pinfunction "P$1_P2") (pintype "passive"))
    )
    (net (code "45") (name "MCBMB09(0)") (class "Default")
      (node (ref "EDGE3") (pin "S2") (pinfunction "1_S2") (pintype "bidirectional"))
      (node (ref "IC8") (pin "4") (pinfunction "A2_4") (pintype "input"))
      (node (ref "SV1") (pin "28") (pinfunction "28_28") (pintype "passive"))
      (node (ref "SV2") (pin "28") (pinfunction "28_28") (pintype "passive"))
      (node (ref "SV3") (pin "28") (pinfunction "28_28") (pintype "passive"))
      (node (ref "SV4") (pin "28") (pinfunction "28_28") (pintype "passive"))
      (node (ref "U$3") (pin "S2") (pinfunction "P$1_S2") (pintype "passive"))
    )
    (net (code "46") (name "MCBMB10(0)") (class "Default")
      (node (ref "EDGE3") (pin "T2") (pinfunction "1_T2") (pintype "bidirectional"))
      (node (ref "IC8") (pin "6") (pinfunction "A3_6") (pintype "input"))
      (node (ref "SV1") (pin "29") (pinfunction "29_29") (pintype "passive"))
      (node (ref "SV2") (pin "29") (pinfunction "29_29") (pintype "passive"))
      (node (ref "SV3") (pin "29") (pinfunction "29_29") (pintype "passive"))
      (node (ref "SV4") (pin "29") (pinfunction "29_29") (pintype "passive"))
      (node (ref "U$3") (pin "T2") (pinfunction "P$1_T2") (pintype "passive"))
    )
    (net (code "47") (name "MCBMB11(0)") (class "Default")
      (node (ref "EDGE3") (pin "V2") (pinfunction "1_V2") (pintype "bidirectional"))
      (node (ref "IC8") (pin "8") (pinfunction "A4_8") (pintype "input"))
      (node (ref "SV1") (pin "30") (pinfunction "30_30") (pintype "passive"))
      (node (ref "SV2") (pin "30") (pinfunction "30_30") (pintype "passive"))
      (node (ref "SV3") (pin "30") (pinfunction "30_30") (pintype "passive"))
      (node (ref "SV4") (pin "30") (pinfunction "30_30") (pintype "passive"))
      (node (ref "U$3") (pin "V2") (pinfunction "P$1_V2") (pintype "passive"))
    )
    (net (code "48") (name "MEM00") (class "Default")
      (node (ref "IC6") (pin "18") (pinfunction "Y1_18") (pintype "tri_state"))
      (node (ref "SV1") (pin "32") (pinfunction "32_32") (pintype "passive"))
      (node (ref "SV2") (pin "32") (pinfunction "32_32") (pintype "passive"))
      (node (ref "SV3") (pin "32") (pinfunction "32_32") (pintype "passive"))
      (node (ref "SV4") (pin "32") (pinfunction "32_32") (pintype "passive"))
    )
    (net (code "49") (name "MEM01") (class "Default")
      (node (ref "IC6") (pin "16") (pinfunction "Y2_16") (pintype "tri_state"))
      (node (ref "SV1") (pin "33") (pinfunction "33_33") (pintype "passive"))
      (node (ref "SV2") (pin "33") (pinfunction "33_33") (pintype "passive"))
      (node (ref "SV3") (pin "33") (pinfunction "33_33") (pintype "passive"))
      (node (ref "SV4") (pin "33") (pinfunction "33_33") (pintype "passive"))
    )
    (net (code "50") (name "MEM02") (class "Default")
      (node (ref "IC6") (pin "14") (pinfunction "Y3_14") (pintype "tri_state"))
      (node (ref "SV1") (pin "34") (pinfunction "34_34") (pintype "passive"))
      (node (ref "SV2") (pin "34") (pinfunction "34_34") (pintype "passive"))
      (node (ref "SV3") (pin "34") (pinfunction "34_34") (pintype "passive"))
      (node (ref "SV4") (pin "34") (pinfunction "34_34") (pintype "passive"))
    )
    (net (code "51") (name "MEM03") (class "Default")
      (node (ref "IC6") (pin "12") (pinfunction "Y4_12") (pintype "tri_state"))
      (node (ref "SV1") (pin "35") (pinfunction "35_35") (pintype "passive"))
      (node (ref "SV2") (pin "35") (pinfunction "35_35") (pintype "passive"))
      (node (ref "SV3") (pin "35") (pinfunction "35_35") (pintype "passive"))
      (node (ref "SV4") (pin "35") (pinfunction "35_35") (pintype "passive"))
    )
    (net (code "52") (name "MEM04") (class "Default")
      (node (ref "IC6") (pin "9") (pinfunction "Y1_9") (pintype "tri_state"))
      (node (ref "SV1") (pin "36") (pinfunction "36_36") (pintype "passive"))
      (node (ref "SV2") (pin "36") (pinfunction "36_36") (pintype "passive"))
      (node (ref "SV3") (pin "36") (pinfunction "36_36") (pintype "passive"))
      (node (ref "SV4") (pin "36") (pinfunction "36_36") (pintype "passive"))
    )
    (net (code "53") (name "MEM05") (class "Default")
      (node (ref "IC6") (pin "7") (pinfunction "Y2_7") (pintype "tri_state"))
      (node (ref "SV1") (pin "37") (pinfunction "37_37") (pintype "passive"))
      (node (ref "SV2") (pin "37") (pinfunction "37_37") (pintype "passive"))
      (node (ref "SV3") (pin "37") (pinfunction "37_37") (pintype "passive"))
      (node (ref "SV4") (pin "37") (pinfunction "37_37") (pintype "passive"))
    )
    (net (code "54") (name "MEM06") (class "Default")
      (node (ref "IC6") (pin "5") (pinfunction "Y3_5") (pintype "tri_state"))
      (node (ref "SV1") (pin "38") (pinfunction "38_38") (pintype "passive"))
      (node (ref "SV2") (pin "38") (pinfunction "38_38") (pintype "passive"))
      (node (ref "SV3") (pin "38") (pinfunction "38_38") (pintype "passive"))
      (node (ref "SV4") (pin "38") (pinfunction "38_38") (pintype "passive"))
    )
    (net (code "55") (name "MEM07") (class "Default")
      (node (ref "IC6") (pin "3") (pinfunction "Y4_3") (pintype "tri_state"))
      (node (ref "SV1") (pin "39") (pinfunction "39_39") (pintype "passive"))
      (node (ref "SV2") (pin "39") (pinfunction "39_39") (pintype "passive"))
      (node (ref "SV3") (pin "39") (pinfunction "39_39") (pintype "passive"))
      (node (ref "SV4") (pin "39") (pinfunction "39_39") (pintype "passive"))
    )
    (net (code "56") (name "MEM08") (class "Default")
      (node (ref "EDGE5") (pin "D2") (pinfunction "1_D2") (pintype "bidirectional"))
      (node (ref "IC7") (pin "18") (pinfunction "Y1_18") (pintype "tri_state"))
      (node (ref "SV1") (pin "40") (pinfunction "40_40") (pintype "passive"))
      (node (ref "SV2") (pin "40") (pinfunction "40_40") (pintype "passive"))
      (node (ref "SV3") (pin "40") (pinfunction "40_40") (pintype "passive"))
      (node (ref "SV4") (pin "40") (pinfunction "40_40") (pintype "passive"))
      (node (ref "U$5") (pin "D2") (pinfunction "P$1_D2") (pintype "passive"))
    )
    (net (code "57") (name "MEM09") (class "Default")
      (node (ref "EDGE5") (pin "E2") (pinfunction "1_E2") (pintype "bidirectional"))
      (node (ref "IC7") (pin "16") (pinfunction "Y2_16") (pintype "tri_state"))
      (node (ref "SV1") (pin "41") (pinfunction "41_41") (pintype "passive"))
      (node (ref "SV2") (pin "41") (pinfunction "41_41") (pintype "passive"))
      (node (ref "SV3") (pin "41") (pinfunction "41_41") (pintype "passive"))
      (node (ref "SV4") (pin "41") (pinfunction "41_41") (pintype "passive"))
      (node (ref "U$5") (pin "E2") (pinfunction "P$1_E2") (pintype "passive"))
    )
    (net (code "58") (name "MEM10") (class "Default")
      (node (ref "EDGE5") (pin "H2") (pinfunction "1_H2") (pintype "bidirectional"))
      (node (ref "IC7") (pin "14") (pinfunction "Y3_14") (pintype "tri_state"))
      (node (ref "SV1") (pin "42") (pinfunction "42_42") (pintype "passive"))
      (node (ref "SV2") (pin "42") (pinfunction "42_42") (pintype "passive"))
      (node (ref "SV3") (pin "42") (pinfunction "42_42") (pintype "passive"))
      (node (ref "SV4") (pin "42") (pinfunction "42_42") (pintype "passive"))
      (node (ref "U$5") (pin "H2") (pinfunction "P$1_H2") (pintype "passive"))
    )
    (net (code "59") (name "MEM11") (class "Default")
      (node (ref "EDGE5") (pin "K2") (pinfunction "1_K2") (pintype "bidirectional"))
      (node (ref "IC7") (pin "12") (pinfunction "Y4_12") (pintype "tri_state"))
      (node (ref "SV1") (pin "43") (pinfunction "43_43") (pintype "passive"))
      (node (ref "SV2") (pin "43") (pinfunction "43_43") (pintype "passive"))
      (node (ref "SV3") (pin "43") (pinfunction "43_43") (pintype "passive"))
      (node (ref "SV4") (pin "43") (pinfunction "43_43") (pintype "passive"))
      (node (ref "U$5") (pin "K2") (pinfunction "P$1_K2") (pintype "passive"))
    )
    (net (code "60") (name "MEMDONE(1)") (class "Default")
      (node (ref "EDGE5") (pin "S2") (pinfunction "1_S2") (pintype "bidirectional"))
      (node (ref "IC10") (pin "9") (pinfunction "Q_9") (pintype "output"))
      (node (ref "SV1") (pin "46") (pinfunction "46_46") (pintype "passive"))
      (node (ref "SV2") (pin "46") (pinfunction "46_46") (pintype "passive"))
      (node (ref "SV3") (pin "46") (pinfunction "46_46") (pintype "passive"))
      (node (ref "SV4") (pin "46") (pinfunction "46_46") (pintype "passive"))
      (node (ref "U$5") (pin "S2") (pinfunction "P$1_S2") (pintype "passive"))
    )
    (net (code "61") (name "MEMSTART(0)") (class "Default")
      (node (ref "EDGE5") (pin "M2") (pinfunction "1_M2") (pintype "bidirectional"))
      (node (ref "IC11") (pin "1") (pinfunction "A_1") (pintype "input"))
      (node (ref "IC3") (pin "12") (pinfunction "I0_12") (pintype "input"))
      (node (ref "IC3") (pin "13") (pinfunction "I1_13") (pintype "input"))
      (node (ref "IC5") (pin "12") (pinfunction "I0_12") (pintype "input"))
      (node (ref "IC5") (pin "13") (pinfunction "I1_13") (pintype "input"))
      (node (ref "IC9") (pin "2") (pinfunction "D_2") (pintype "input"))
      (node (ref "SV1") (pin "44") (pinfunction "44_44") (pintype "passive"))
      (node (ref "SV2") (pin "44") (pinfunction "44_44") (pintype "passive"))
      (node (ref "SV3") (pin "44") (pinfunction "44_44") (pintype "passive"))
      (node (ref "SV4") (pin "44") (pinfunction "44_44") (pintype "passive"))
      (node (ref "U$5") (pin "M2") (pinfunction "P$1_M2") (pintype "passive"))
    )
    (net (code "62") (name "MEMSTART(1)") (class "Default")
      (node (ref "IC3") (pin "11") (pinfunction "O_11") (pintype "output"))
      (node (ref "IC3") (pin "9") (pinfunction "I0_9") (pintype "input"))
    )
    (net (code "63") (name "MEMSTART(1)2") (class "Default")
      (node (ref "IC5") (pin "10") (pinfunction "I1_10") (pintype "input"))
      (node (ref "IC5") (pin "11") (pinfunction "O_11") (pintype "output"))
    )
    (net (code "64") (name "MEM_P") (class "Default")
      (node (ref "IC7") (pin "9") (pinfunction "Y1_9") (pintype "tri_state"))
      (node (ref "SV1") (pin "31") (pinfunction "31_31") (pintype "passive"))
      (node (ref "SV2") (pin "31") (pinfunction "31_31") (pintype "passive"))
      (node (ref "SV3") (pin "31") (pinfunction "31_31") (pintype "passive"))
      (node (ref "SV4") (pin "31") (pinfunction "31_31") (pintype "passive"))
    )
    (net (code "65") (name "Net-(EDGE1A-1)") (class "Default")
      (node (ref "EDGE1") (pin "A1") (pinfunction "1_A1") (pintype "bidirectional"))
      (node (ref "U$1") (pin "A1") (pinfunction "P$1_A1") (pintype "passive"))
    )
    (net (code "66") (name "Net-(EDGE1AA-1)") (class "Default")
      (node (ref "EDGE1") (pin "R1") (pinfunction "1_R1") (pintype "bidirectional"))
      (node (ref "U$1") (pin "R1") (pinfunction "P$1_R1") (pintype "passive"))
    )
    (net (code "67") (name "Net-(EDGE1AB-1)") (class "Default")
      (node (ref "EDGE1") (pin "R2") (pinfunction "1_R2") (pintype "bidirectional"))
      (node (ref "U$1") (pin "R2") (pinfunction "P$1_R2") (pintype "passive"))
    )
    (net (code "68") (name "Net-(EDGE1AC-1)") (class "Default")
      (node (ref "EDGE1") (pin "S1") (pinfunction "1_S1") (pintype "bidirectional"))
      (node (ref "U$1") (pin "S1") (pinfunction "P$1_S1") (pintype "passive"))
    )
    (net (code "69") (name "Net-(EDGE1AE-1)") (class "Default")
      (node (ref "EDGE1") (pin "T1") (pinfunction "1_T1") (pintype "bidirectional"))
      (node (ref "U$1") (pin "T1") (pinfunction "P$1_T1") (pintype "passive"))
    )
    (net (code "70") (name "Net-(EDGE1AG-1)") (class "Default")
      (node (ref "EDGE1") (pin "U1") (pinfunction "1_U1") (pintype "bidirectional"))
      (node (ref "U$1") (pin "U1") (pinfunction "P$1_U1") (pintype "passive"))
    )
    (net (code "71") (name "Net-(EDGE1AH-1)") (class "Default")
      (node (ref "EDGE1") (pin "U2") (pinfunction "1_U2") (pintype "bidirectional"))
      (node (ref "U$1") (pin "U2") (pinfunction "P$1_U2") (pintype "passive"))
    )
    (net (code "72") (name "Net-(EDGE1AI-1)") (class "Default")
      (node (ref "EDGE1") (pin "V1") (pinfunction "1_V1") (pintype "bidirectional"))
      (node (ref "U$1") (pin "V1") (pinfunction "P$1_V1") (pintype "passive"))
    )
    (net (code "73") (name "Net-(EDGE1C-1)") (class "Default")
      (node (ref "EDGE1") (pin "B1") (pinfunction "1_B1") (pintype "bidirectional"))
      (node (ref "U$1") (pin "B1") (pinfunction "P$1_B1") (pintype "passive"))
    )
    (net (code "74") (name "Net-(EDGE1D-1)") (class "Default")
      (node (ref "EDGE1") (pin "B2") (pinfunction "1_B2") (pintype "bidirectional"))
      (node (ref "U$1") (pin "B2") (pinfunction "P$1_B2") (pintype "passive"))
    )
    (net (code "75") (name "Net-(EDGE1E-1)") (class "Default")
      (node (ref "EDGE1") (pin "C1") (pinfunction "1_C1") (pintype "bidirectional"))
      (node (ref "U$1") (pin "C1") (pinfunction "P$1_C1") (pintype "passive"))
    )
    (net (code "76") (name "Net-(EDGE1G-1)") (class "Default")
      (node (ref "EDGE1") (pin "D1") (pinfunction "1_D1") (pintype "bidirectional"))
      (node (ref "U$1") (pin "D1") (pinfunction "P$1_D1") (pintype "passive"))
    )
    (net (code "77") (name "Net-(EDGE1I-1)") (class "Default")
      (node (ref "EDGE1") (pin "E1") (pinfunction "1_E1") (pintype "bidirectional"))
      (node (ref "U$1") (pin "E1") (pinfunction "P$1_E1") (pintype "passive"))
    )
    (net (code "78") (name "Net-(EDGE1K-1)") (class "Default")
      (node (ref "EDGE1") (pin "F1") (pinfunction "1_F1") (pintype "bidirectional"))
      (node (ref "U$1") (pin "F1") (pinfunction "P$1_F1") (pintype "passive"))
    )
    (net (code "79") (name "Net-(EDGE1L-1)") (class "Default")
      (node (ref "EDGE1") (pin "F2") (pinfunction "1_F2") (pintype "bidirectional"))
      (node (ref "U$1") (pin "F2") (pinfunction "P$1_F2") (pintype "passive"))
    )
    (net (code "80") (name "Net-(EDGE1M-1)") (class "Default")
      (node (ref "EDGE1") (pin "H1") (pinfunction "1_H1") (pintype "bidirectional"))
      (node (ref "U$1") (pin "H1") (pinfunction "P$1_H1") (pintype "passive"))
    )
    (net (code "81") (name "Net-(EDGE1O-1)") (class "Default")
      (node (ref "EDGE1") (pin "J1") (pinfunction "1_J1") (pintype "bidirectional"))
      (node (ref "U$1") (pin "J1") (pinfunction "P$1_J1") (pintype "passive"))
    )
    (net (code "82") (name "Net-(EDGE1P-1)") (class "Default")
      (node (ref "EDGE1") (pin "J2") (pinfunction "1_J2") (pintype "bidirectional"))
      (node (ref "U$1") (pin "J2") (pinfunction "P$1_J2") (pintype "passive"))
    )
    (net (code "83") (name "Net-(EDGE1Q-1)") (class "Default")
      (node (ref "EDGE1") (pin "K1") (pinfunction "1_K1") (pintype "bidirectional"))
      (node (ref "U$1") (pin "K1") (pinfunction "P$1_K1") (pintype "passive"))
    )
    (net (code "84") (name "Net-(EDGE1S-1)") (class "Default")
      (node (ref "EDGE1") (pin "L1") (pinfunction "1_L1") (pintype "bidirectional"))
      (node (ref "U$1") (pin "L1") (pinfunction "P$1_L1") (pintype "passive"))
    )
    (net (code "85") (name "Net-(EDGE1T-1)") (class "Default")
      (node (ref "EDGE1") (pin "L2") (pinfunction "1_L2") (pintype "bidirectional"))
      (node (ref "U$1") (pin "L2") (pinfunction "P$1_L2") (pintype "passive"))
    )
    (net (code "86") (name "Net-(EDGE1U-1)") (class "Default")
      (node (ref "EDGE1") (pin "M1") (pinfunction "1_M1") (pintype "bidirectional"))
      (node (ref "U$1") (pin "M1") (pinfunction "P$1_M1") (pintype "passive"))
    )
    (net (code "87") (name "Net-(EDGE1W-1)") (class "Default")
      (node (ref "EDGE1") (pin "N1") (pinfunction "1_N1") (pintype "bidirectional"))
      (node (ref "U$1") (pin "N1") (pinfunction "P$1_N1") (pintype "passive"))
    )
    (net (code "88") (name "Net-(EDGE1X-1)") (class "Default")
      (node (ref "EDGE1") (pin "N2") (pinfunction "1_N2") (pintype "bidirectional"))
      (node (ref "U$1") (pin "N2") (pinfunction "P$1_N2") (pintype "passive"))
    )
    (net (code "89") (name "Net-(EDGE1Y-1)") (class "Default")
      (node (ref "EDGE1") (pin "P1") (pinfunction "1_P1") (pintype "bidirectional"))
      (node (ref "U$1") (pin "P1") (pinfunction "P$1_P1") (pintype "passive"))
    )
    (net (code "90") (name "Net-(EDGE2A-1)") (class "Default")
      (node (ref "EDGE2") (pin "A1") (pinfunction "1_A1") (pintype "bidirectional"))
      (node (ref "U$2") (pin "A1") (pinfunction "P$1_A1") (pintype "passive"))
    )
    (net (code "91") (name "Net-(EDGE2AA-1)") (class "Default")
      (node (ref "EDGE2") (pin "R1") (pinfunction "1_R1") (pintype "bidirectional"))
      (node (ref "U$2") (pin "R1") (pinfunction "P$1_R1") (pintype "passive"))
    )
    (net (code "92") (name "Net-(EDGE2AB-1)") (class "Default")
      (node (ref "EDGE2") (pin "R2") (pinfunction "1_R2") (pintype "bidirectional"))
      (node (ref "U$2") (pin "R2") (pinfunction "P$1_R2") (pintype "passive"))
    )
    (net (code "93") (name "Net-(EDGE2AC-1)") (class "Default")
      (node (ref "EDGE2") (pin "S1") (pinfunction "1_S1") (pintype "bidirectional"))
      (node (ref "U$2") (pin "S1") (pinfunction "P$1_S1") (pintype "passive"))
    )
    (net (code "94") (name "Net-(EDGE2AE-1)") (class "Default")
      (node (ref "EDGE2") (pin "T1") (pinfunction "1_T1") (pintype "bidirectional"))
      (node (ref "U$2") (pin "T1") (pinfunction "P$1_T1") (pintype "passive"))
    )
    (net (code "95") (name "Net-(EDGE2AG-1)") (class "Default")
      (node (ref "EDGE2") (pin "U1") (pinfunction "1_U1") (pintype "bidirectional"))
      (node (ref "U$2") (pin "U1") (pinfunction "P$1_U1") (pintype "passive"))
    )
    (net (code "96") (name "Net-(EDGE2AH-1)") (class "Default")
      (node (ref "EDGE2") (pin "U2") (pinfunction "1_U2") (pintype "bidirectional"))
      (node (ref "U$2") (pin "U2") (pinfunction "P$1_U2") (pintype "passive"))
    )
    (net (code "97") (name "Net-(EDGE2AI-1)") (class "Default")
      (node (ref "EDGE2") (pin "V1") (pinfunction "1_V1") (pintype "bidirectional"))
      (node (ref "U$2") (pin "V1") (pinfunction "P$1_V1") (pintype "passive"))
    )
    (net (code "98") (name "Net-(EDGE2C-1)") (class "Default")
      (node (ref "EDGE2") (pin "B1") (pinfunction "1_B1") (pintype "bidirectional"))
      (node (ref "U$2") (pin "B1") (pinfunction "P$1_B1") (pintype "passive"))
    )
    (net (code "99") (name "Net-(EDGE2D-1)") (class "Default")
      (node (ref "EDGE2") (pin "B2") (pinfunction "1_B2") (pintype "bidirectional"))
      (node (ref "U$2") (pin "B2") (pinfunction "P$1_B2") (pintype "passive"))
    )
    (net (code "100") (name "Net-(EDGE2E-1)") (class "Default")
      (node (ref "EDGE2") (pin "C1") (pinfunction "1_C1") (pintype "bidirectional"))
      (node (ref "U$2") (pin "C1") (pinfunction "P$1_C1") (pintype "passive"))
    )
    (net (code "101") (name "Net-(EDGE2G-1)") (class "Default")
      (node (ref "EDGE2") (pin "D1") (pinfunction "1_D1") (pintype "bidirectional"))
      (node (ref "U$2") (pin "D1") (pinfunction "P$1_D1") (pintype "passive"))
    )
    (net (code "102") (name "Net-(EDGE2I-1)") (class "Default")
      (node (ref "EDGE2") (pin "E1") (pinfunction "1_E1") (pintype "bidirectional"))
      (node (ref "U$2") (pin "E1") (pinfunction "P$1_E1") (pintype "passive"))
    )
    (net (code "103") (name "Net-(EDGE2K-1)") (class "Default")
      (node (ref "EDGE2") (pin "F1") (pinfunction "1_F1") (pintype "bidirectional"))
      (node (ref "U$2") (pin "F1") (pinfunction "P$1_F1") (pintype "passive"))
    )
    (net (code "104") (name "Net-(EDGE2L-1)") (class "Default")
      (node (ref "EDGE2") (pin "F2") (pinfunction "1_F2") (pintype "bidirectional"))
      (node (ref "U$2") (pin "F2") (pinfunction "P$1_F2") (pintype "passive"))
    )
    (net (code "105") (name "Net-(EDGE2M-1)") (class "Default")
      (node (ref "EDGE2") (pin "H1") (pinfunction "1_H1") (pintype "bidirectional"))
      (node (ref "U$2") (pin "H1") (pinfunction "P$1_H1") (pintype "passive"))
    )
    (net (code "106") (name "Net-(EDGE2O-1)") (class "Default")
      (node (ref "EDGE2") (pin "J1") (pinfunction "1_J1") (pintype "bidirectional"))
      (node (ref "U$2") (pin "J1") (pinfunction "P$1_J1") (pintype "passive"))
    )
    (net (code "107") (name "Net-(EDGE2P-1)") (class "Default")
      (node (ref "EDGE2") (pin "J2") (pinfunction "1_J2") (pintype "bidirectional"))
      (node (ref "U$2") (pin "J2") (pinfunction "P$1_J2") (pintype "passive"))
    )
    (net (code "108") (name "Net-(EDGE2Q-1)") (class "Default")
      (node (ref "EDGE2") (pin "K1") (pinfunction "1_K1") (pintype "bidirectional"))
      (node (ref "U$2") (pin "K1") (pinfunction "P$1_K1") (pintype "passive"))
    )
    (net (code "109") (name "Net-(EDGE2S-1)") (class "Default")
      (node (ref "EDGE2") (pin "L1") (pinfunction "1_L1") (pintype "bidirectional"))
      (node (ref "U$2") (pin "L1") (pinfunction "P$1_L1") (pintype "passive"))
    )
    (net (code "110") (name "Net-(EDGE2T-1)") (class "Default")
      (node (ref "EDGE2") (pin "L2") (pinfunction "1_L2") (pintype "bidirectional"))
      (node (ref "U$2") (pin "L2") (pinfunction "P$1_L2") (pintype "passive"))
    )
    (net (code "111") (name "Net-(EDGE2U-1)") (class "Default")
      (node (ref "EDGE2") (pin "M1") (pinfunction "1_M1") (pintype "bidirectional"))
      (node (ref "U$2") (pin "M1") (pinfunction "P$1_M1") (pintype "passive"))
    )
    (net (code "112") (name "Net-(EDGE2W-1)") (class "Default")
      (node (ref "EDGE2") (pin "N1") (pinfunction "1_N1") (pintype "bidirectional"))
      (node (ref "U$2") (pin "N1") (pinfunction "P$1_N1") (pintype "passive"))
    )
    (net (code "113") (name "Net-(EDGE2X-1)") (class "Default")
      (node (ref "EDGE2") (pin "N2") (pinfunction "1_N2") (pintype "bidirectional"))
      (node (ref "U$2") (pin "N2") (pinfunction "P$1_N2") (pintype "passive"))
    )
    (net (code "114") (name "Net-(EDGE2Y-1)") (class "Default")
      (node (ref "EDGE2") (pin "P1") (pinfunction "1_P1") (pintype "bidirectional"))
      (node (ref "U$2") (pin "P1") (pinfunction "P$1_P1") (pintype "passive"))
    )
    (net (code "115") (name "Net-(EDGE3A-1)") (class "Default")
      (node (ref "EDGE3") (pin "A1") (pinfunction "1_A1") (pintype "bidirectional"))
      (node (ref "U$3") (pin "A1") (pinfunction "P$1_A1") (pintype "passive"))
    )
    (net (code "116") (name "Net-(EDGE3AA-1)") (class "Default")
      (node (ref "EDGE3") (pin "R1") (pinfunction "1_R1") (pintype "bidirectional"))
      (node (ref "U$3") (pin "R1") (pinfunction "P$1_R1") (pintype "passive"))
    )
    (net (code "117") (name "Net-(EDGE3AB-1)") (class "Default")
      (node (ref "EDGE3") (pin "R2") (pinfunction "1_R2") (pintype "bidirectional"))
      (node (ref "U$3") (pin "R2") (pinfunction "P$1_R2") (pintype "passive"))
    )
    (net (code "118") (name "Net-(EDGE3AC-1)") (class "Default")
      (node (ref "EDGE3") (pin "S1") (pinfunction "1_S1") (pintype "bidirectional"))
      (node (ref "U$3") (pin "S1") (pinfunction "P$1_S1") (pintype "passive"))
    )
    (net (code "119") (name "Net-(EDGE3AE-1)") (class "Default")
      (node (ref "EDGE3") (pin "T1") (pinfunction "1_T1") (pintype "bidirectional"))
      (node (ref "U$3") (pin "T1") (pinfunction "P$1_T1") (pintype "passive"))
    )
    (net (code "120") (name "Net-(EDGE3AG-1)") (class "Default")
      (node (ref "EDGE3") (pin "U1") (pinfunction "1_U1") (pintype "bidirectional"))
      (node (ref "U$3") (pin "U1") (pinfunction "P$1_U1") (pintype "passive"))
    )
    (net (code "121") (name "Net-(EDGE3AH-1)") (class "Default")
      (node (ref "EDGE3") (pin "U2") (pinfunction "1_U2") (pintype "bidirectional"))
      (node (ref "U$3") (pin "U2") (pinfunction "P$1_U2") (pintype "passive"))
    )
    (net (code "122") (name "Net-(EDGE3AI-1)") (class "Default")
      (node (ref "EDGE3") (pin "V1") (pinfunction "1_V1") (pintype "bidirectional"))
      (node (ref "U$3") (pin "V1") (pinfunction "P$1_V1") (pintype "passive"))
    )
    (net (code "123") (name "Net-(EDGE3C-1)") (class "Default")
      (node (ref "EDGE3") (pin "B1") (pinfunction "1_B1") (pintype "bidirectional"))
      (node (ref "U$3") (pin "B1") (pinfunction "P$1_B1") (pintype "passive"))
    )
    (net (code "124") (name "Net-(EDGE3D-1)") (class "Default")
      (node (ref "EDGE3") (pin "B2") (pinfunction "1_B2") (pintype "bidirectional"))
      (node (ref "U$3") (pin "B2") (pinfunction "P$1_B2") (pintype "passive"))
    )
    (net (code "125") (name "Net-(EDGE3E-1)") (class "Default")
      (node (ref "EDGE3") (pin "C1") (pinfunction "1_C1") (pintype "bidirectional"))
      (node (ref "U$3") (pin "C1") (pinfunction "P$1_C1") (pintype "passive"))
    )
    (net (code "126") (name "Net-(EDGE3G-1)") (class "Default")
      (node (ref "EDGE3") (pin "D1") (pinfunction "1_D1") (pintype "bidirectional"))
      (node (ref "U$3") (pin "D1") (pinfunction "P$1_D1") (pintype "passive"))
    )
    (net (code "127") (name "Net-(EDGE3I-1)") (class "Default")
      (node (ref "EDGE3") (pin "E1") (pinfunction "1_E1") (pintype "bidirectional"))
      (node (ref "U$3") (pin "E1") (pinfunction "P$1_E1") (pintype "passive"))
    )
    (net (code "128") (name "Net-(EDGE3K-1)") (class "Default")
      (node (ref "EDGE3") (pin "F1") (pinfunction "1_F1") (pintype "bidirectional"))
      (node (ref "U$3") (pin "F1") (pinfunction "P$1_F1") (pintype "passive"))
    )
    (net (code "129") (name "Net-(EDGE3L-1)") (class "Default")
      (node (ref "EDGE3") (pin "F2") (pinfunction "1_F2") (pintype "bidirectional"))
      (node (ref "U$3") (pin "F2") (pinfunction "P$1_F2") (pintype "passive"))
    )
    (net (code "130") (name "Net-(EDGE3M-1)") (class "Default")
      (node (ref "EDGE3") (pin "H1") (pinfunction "1_H1") (pintype "bidirectional"))
      (node (ref "U$3") (pin "H1") (pinfunction "P$1_H1") (pintype "passive"))
    )
    (net (code "131") (name "Net-(EDGE3O-1)") (class "Default")
      (node (ref "EDGE3") (pin "J1") (pinfunction "1_J1") (pintype "bidirectional"))
      (node (ref "U$3") (pin "J1") (pinfunction "P$1_J1") (pintype "passive"))
    )
    (net (code "132") (name "Net-(EDGE3P-1)") (class "Default")
      (node (ref "EDGE3") (pin "J2") (pinfunction "1_J2") (pintype "bidirectional"))
      (node (ref "U$3") (pin "J2") (pinfunction "P$1_J2") (pintype "passive"))
    )
    (net (code "133") (name "Net-(EDGE3Q-1)") (class "Default")
      (node (ref "EDGE3") (pin "K1") (pinfunction "1_K1") (pintype "bidirectional"))
      (node (ref "U$3") (pin "K1") (pinfunction "P$1_K1") (pintype "passive"))
    )
    (net (code "134") (name "Net-(EDGE3S-1)") (class "Default")
      (node (ref "EDGE3") (pin "L1") (pinfunction "1_L1") (pintype "bidirectional"))
      (node (ref "U$3") (pin "L1") (pinfunction "P$1_L1") (pintype "passive"))
    )
    (net (code "135") (name "Net-(EDGE3T-1)") (class "Default")
      (node (ref "EDGE3") (pin "L2") (pinfunction "1_L2") (pintype "bidirectional"))
      (node (ref "U$3") (pin "L2") (pinfunction "P$1_L2") (pintype "passive"))
    )
    (net (code "136") (name "Net-(EDGE3U-1)") (class "Default")
      (node (ref "EDGE3") (pin "M1") (pinfunction "1_M1") (pintype "bidirectional"))
      (node (ref "U$3") (pin "M1") (pinfunction "P$1_M1") (pintype "passive"))
    )
    (net (code "137") (name "Net-(EDGE3W-1)") (class "Default")
      (node (ref "EDGE3") (pin "N1") (pinfunction "1_N1") (pintype "bidirectional"))
      (node (ref "U$3") (pin "N1") (pinfunction "P$1_N1") (pintype "passive"))
    )
    (net (code "138") (name "Net-(EDGE3X-1)") (class "Default")
      (node (ref "EDGE3") (pin "N2") (pinfunction "1_N2") (pintype "bidirectional"))
      (node (ref "U$3") (pin "N2") (pinfunction "P$1_N2") (pintype "passive"))
    )
    (net (code "139") (name "Net-(EDGE3Y-1)") (class "Default")
      (node (ref "EDGE3") (pin "P1") (pinfunction "1_P1") (pintype "bidirectional"))
      (node (ref "U$3") (pin "P1") (pinfunction "P$1_P1") (pintype "passive"))
    )
    (net (code "140") (name "Net-(EDGE5A-1)") (class "Default")
      (node (ref "EDGE5") (pin "A1") (pinfunction "1_A1") (pintype "bidirectional"))
      (node (ref "U$5") (pin "A1") (pinfunction "P$1_A1") (pintype "passive"))
    )
    (net (code "141") (name "Net-(EDGE5AA-1)") (class "Default")
      (node (ref "EDGE5") (pin "R1") (pinfunction "1_R1") (pintype "bidirectional"))
      (node (ref "U$5") (pin "R1") (pinfunction "P$1_R1") (pintype "passive"))
    )
    (net (code "142") (name "Net-(EDGE5AB-1)") (class "Default")
      (node (ref "EDGE5") (pin "R2") (pinfunction "1_R2") (pintype "bidirectional"))
      (node (ref "U$5") (pin "R2") (pinfunction "P$1_R2") (pintype "passive"))
    )
    (net (code "143") (name "Net-(EDGE5AC-1)") (class "Default")
      (node (ref "EDGE5") (pin "S1") (pinfunction "1_S1") (pintype "bidirectional"))
      (node (ref "U$5") (pin "S1") (pinfunction "P$1_S1") (pintype "passive"))
    )
    (net (code "144") (name "Net-(EDGE5AE-1)") (class "Default")
      (node (ref "EDGE5") (pin "T1") (pinfunction "1_T1") (pintype "bidirectional"))
      (node (ref "U$5") (pin "T1") (pinfunction "P$1_T1") (pintype "passive"))
    )
    (net (code "145") (name "Net-(EDGE5AG-1)") (class "Default")
      (node (ref "EDGE5") (pin "U1") (pinfunction "1_U1") (pintype "bidirectional"))
      (node (ref "U$5") (pin "U1") (pinfunction "P$1_U1") (pintype "passive"))
    )
    (net (code "146") (name "Net-(EDGE5AH-1)") (class "Default")
      (node (ref "EDGE5") (pin "U2") (pinfunction "1_U2") (pintype "bidirectional"))
      (node (ref "U$5") (pin "U2") (pinfunction "P$1_U2") (pintype "passive"))
    )
    (net (code "147") (name "Net-(EDGE5AI-1)") (class "Default")
      (node (ref "EDGE5") (pin "V1") (pinfunction "1_V1") (pintype "bidirectional"))
      (node (ref "U$5") (pin "V1") (pinfunction "P$1_V1") (pintype "passive"))
    )
    (net (code "148") (name "Net-(EDGE5C-1)") (class "Default")
      (node (ref "EDGE5") (pin "B1") (pinfunction "1_B1") (pintype "bidirectional"))
      (node (ref "U$5") (pin "B1") (pinfunction "P$1_B1") (pintype "passive"))
    )
    (net (code "149") (name "Net-(EDGE5D-1)") (class "Default")
      (node (ref "EDGE5") (pin "B2") (pinfunction "1_B2") (pintype "bidirectional"))
      (node (ref "U$5") (pin "B2") (pinfunction "P$1_B2") (pintype "passive"))
    )
    (net (code "150") (name "Net-(EDGE5E-1)") (class "Default")
      (node (ref "EDGE5") (pin "C1") (pinfunction "1_C1") (pintype "bidirectional"))
      (node (ref "U$5") (pin "C1") (pinfunction "P$1_C1") (pintype "passive"))
    )
    (net (code "151") (name "Net-(EDGE5G-1)") (class "Default")
      (node (ref "EDGE5") (pin "D1") (pinfunction "1_D1") (pintype "bidirectional"))
      (node (ref "U$5") (pin "D1") (pinfunction "P$1_D1") (pintype "passive"))
    )
    (net (code "152") (name "Net-(EDGE5I-1)") (class "Default")
      (node (ref "EDGE5") (pin "E1") (pinfunction "1_E1") (pintype "bidirectional"))
      (node (ref "U$5") (pin "E1") (pinfunction "P$1_E1") (pintype "passive"))
    )
    (net (code "153") (name "Net-(EDGE5K-1)") (class "Default")
      (node (ref "EDGE5") (pin "F1") (pinfunction "1_F1") (pintype "bidirectional"))
      (node (ref "U$5") (pin "F1") (pinfunction "P$1_F1") (pintype "passive"))
    )
    (net (code "154") (name "Net-(EDGE5L-1)") (class "Default")
      (node (ref "EDGE5") (pin "F2") (pinfunction "1_F2") (pintype "bidirectional"))
      (node (ref "U$5") (pin "F2") (pinfunction "P$1_F2") (pintype "passive"))
    )
    (net (code "155") (name "Net-(EDGE5M-1)") (class "Default")
      (node (ref "EDGE5") (pin "H1") (pinfunction "1_H1") (pintype "bidirectional"))
      (node (ref "U$5") (pin "H1") (pinfunction "P$1_H1") (pintype "passive"))
    )
    (net (code "156") (name "Net-(EDGE5O-1)") (class "Default")
      (node (ref "EDGE5") (pin "J1") (pinfunction "1_J1") (pintype "bidirectional"))
      (node (ref "U$5") (pin "J1") (pinfunction "P$1_J1") (pintype "passive"))
    )
    (net (code "157") (name "Net-(EDGE5P-1)") (class "Default")
      (node (ref "EDGE5") (pin "J2") (pinfunction "1_J2") (pintype "bidirectional"))
      (node (ref "U$5") (pin "J2") (pinfunction "P$1_J2") (pintype "passive"))
    )
    (net (code "158") (name "Net-(EDGE5Q-1)") (class "Default")
      (node (ref "EDGE5") (pin "K1") (pinfunction "1_K1") (pintype "bidirectional"))
      (node (ref "U$5") (pin "K1") (pinfunction "P$1_K1") (pintype "passive"))
    )
    (net (code "159") (name "Net-(EDGE5S-1)") (class "Default")
      (node (ref "EDGE5") (pin "L1") (pinfunction "1_L1") (pintype "bidirectional"))
      (node (ref "U$5") (pin "L1") (pinfunction "P$1_L1") (pintype "passive"))
    )
    (net (code "160") (name "Net-(EDGE5T-1)") (class "Default")
      (node (ref "EDGE5") (pin "L2") (pinfunction "1_L2") (pintype "bidirectional"))
      (node (ref "U$5") (pin "L2") (pinfunction "P$1_L2") (pintype "passive"))
    )
    (net (code "161") (name "Net-(EDGE5U-1)") (class "Default")
      (node (ref "EDGE5") (pin "M1") (pinfunction "1_M1") (pintype "bidirectional"))
      (node (ref "U$5") (pin "M1") (pinfunction "P$1_M1") (pintype "passive"))
    )
    (net (code "162") (name "Net-(EDGE5W-1)") (class "Default")
      (node (ref "EDGE5") (pin "N1") (pinfunction "1_N1") (pintype "bidirectional"))
      (node (ref "U$5") (pin "N1") (pinfunction "P$1_N1") (pintype "passive"))
    )
    (net (code "163") (name "Net-(EDGE5X-1)") (class "Default")
      (node (ref "EDGE5") (pin "N2") (pinfunction "1_N2") (pintype "bidirectional"))
      (node (ref "U$5") (pin "N2") (pinfunction "P$1_N2") (pintype "passive"))
    )
    (net (code "164") (name "Net-(EDGE5Y-1)") (class "Default")
      (node (ref "EDGE5") (pin "P1") (pinfunction "1_P1") (pintype "bidirectional"))
      (node (ref "U$5") (pin "P1") (pinfunction "P$1_P1") (pintype "passive"))
    )
    (net (code "165") (name "Net-(IC7B-A2)") (class "Default")
      (node (ref "IC7") (pin "13") (pinfunction "A2_13") (pintype "input"))
      (node (ref "IC8") (pin "7") (pinfunction "Y2_7") (pintype "tri_state"))
    )
    (net (code "166") (name "Net-(IC7B-A3)") (class "Default")
      (node (ref "IC7") (pin "15") (pinfunction "A3_15") (pintype "input"))
      (node (ref "IC8") (pin "5") (pinfunction "Y3_5") (pintype "tri_state"))
    )
    (net (code "167") (name "Net-(IC7B-A4)") (class "Default")
      (node (ref "IC7") (pin "17") (pinfunction "A4_17") (pintype "input"))
      (node (ref "IC8") (pin "3") (pinfunction "Y4_3") (pintype "tri_state"))
    )
    (net (code "168") (name "Net-(IC10A-D)") (class "Default")
      (node (ref "IC10") (pin "2") (pinfunction "D_2") (pintype "input"))
      (node (ref "IC9") (pin "5") (pinfunction "Q_5") (pintype "output"))
    )
    (net (code "169") (name "Net-(IC10A-Q)") (class "Default")
      (node (ref "IC10") (pin "12") (pinfunction "D_12") (pintype "input"))
      (node (ref "IC10") (pin "5") (pinfunction "Q_5") (pintype "output"))
    )
    (net (code "170") (name "Net-(IC11A-B)") (class "Default")
      (node (ref "IC11") (pin "2") (pinfunction "B_2") (pintype "input"))
      (node (ref "IC11") (pin "4") (pinfunction "~{Q}_4") (pintype "output"))
    )
    (net (code "171") (name "Net-(IC11A-C)") (class "Default")
      (node (ref "C4") (pin "2") (pinfunction "2_2") (pintype "passive"))
      (node (ref "IC11") (pin "14") (pinfunction "C_14") (pintype "input"))
    )
    (net (code "172") (name "Net-(IC11A-R{slash}C)") (class "Default")
      (node (ref "C4") (pin "1") (pinfunction "1_1") (pintype "passive"))
      (node (ref "IC11") (pin "15") (pinfunction "R/C_15") (pintype "input"))
      (node (ref "R1") (pin "2") (pinfunction "2_2") (pintype "passive"))
    )
    (net (code "173") (name "OE(0)1") (class "Default")
      (node (ref "IC1") (pin "22") (pinfunction "~{OE}_22") (pintype "input"))
      (node (ref "IC3") (pin "8") (pinfunction "O_8") (pintype "output"))
      (node (ref "IC6") (pin "1") (pinfunction "G_1") (pintype "input"))
      (node (ref "IC6") (pin "19") (pinfunction "G_19") (pintype "input"))
    )
    (net (code "174") (name "OE(0)2") (class "Default")
      (node (ref "IC2") (pin "22") (pinfunction "~{OE}_22") (pintype "input"))
      (node (ref "IC5") (pin "8") (pinfunction "O_8") (pintype "output"))
      (node (ref "IC7") (pin "1") (pinfunction "G_1") (pintype "input"))
      (node (ref "IC7") (pin "19") (pinfunction "G_19") (pintype "input"))
    )
    (net (code "175") (name "PARITY") (class "Default")
      (node (ref "IC2") (pin "16") (pinfunction "I/O4_16") (pintype "bidirectional"))
      (node (ref "IC7") (pin "11") (pinfunction "A1_11") (pintype "input"))
      (node (ref "IC8") (pin "9") (pinfunction "Y1_9") (pintype "tri_state"))
    )
    (net (code "176") (name "STROBE(0)") (class "Default")
      (node (ref "EDGE5") (pin "P2") (pinfunction "1_P2") (pintype "bidirectional"))
      (node (ref "IC9") (pin "6") (pinfunction "~{Q}_6") (pintype "output"))
      (node (ref "SV1") (pin "45") (pinfunction "45_45") (pintype "passive"))
      (node (ref "SV2") (pin "45") (pinfunction "45_45") (pintype "passive"))
      (node (ref "SV3") (pin "45") (pinfunction "45_45") (pintype "passive"))
      (node (ref "SV4") (pin "45") (pinfunction "45_45") (pintype "passive"))
      (node (ref "U$5") (pin "P2") (pinfunction "P$1_P2") (pintype "passive"))
    )
    (net (code "177") (name "VCC") (class "Default")
      (node (ref "C2") (pin "1") (pinfunction "1_1") (pintype "passive"))
      (node (ref "EDGE1") (pin "A2") (pinfunction "1_A2") (pintype "bidirectional"))
      (node (ref "EDGE2") (pin "A2") (pinfunction "1_A2") (pintype "bidirectional"))
      (node (ref "EDGE3") (pin "A2") (pinfunction "1_A2") (pintype "bidirectional"))
      (node (ref "EDGE5") (pin "A2") (pinfunction "1_A2") (pintype "bidirectional"))
      (node (ref "IC1") (pin "28") (pinfunction "VCC_28") (pintype "power_in"))
      (node (ref "IC10") (pin "1") (pinfunction "CLR_1") (pintype "input"))
      (node (ref "IC10") (pin "10") (pinfunction "PRE_10") (pintype "input"))
      (node (ref "IC10") (pin "13") (pinfunction "CLR_13") (pintype "input"))
      (node (ref "IC10") (pin "4") (pinfunction "PRE_4") (pintype "input"))
      (node (ref "IC11") (pin "3") (pinfunction "CLR_3") (pintype "input"))
      (node (ref "IC2") (pin "28") (pinfunction "VCC_28") (pintype "power_in"))
      (node (ref "IC9") (pin "1") (pinfunction "CLR_1") (pintype "input"))
      (node (ref "IC9") (pin "4") (pinfunction "PRE_4") (pintype "input"))
      (node (ref "R1") (pin "1") (pinfunction "1_1") (pintype "passive"))
      (node (ref "U$1") (pin "A2") (pinfunction "P$1_A2") (pintype "passive"))
      (node (ref "U$2") (pin "A2") (pinfunction "P$1_A2") (pintype "passive"))
      (node (ref "U$3") (pin "A2") (pinfunction "P$1_A2") (pintype "passive"))
      (node (ref "U$5") (pin "A2") (pinfunction "P$1_A2") (pintype "passive"))
    )
    (net (code "178") (name "WE(0)") (class "Default")
      (node (ref "IC2") (pin "27") (pinfunction "~{WE}_27") (pintype "input"))
      (node (ref "IC8") (pin "1") (pinfunction "G_1") (pintype "input"))
      (node (ref "IC8") (pin "19") (pinfunction "G_19") (pintype "input"))
      (node (ref "SV1") (pin "3") (pinfunction "3_3") (pintype "passive"))
      (node (ref "SV3") (pin "3") (pinfunction "3_3") (pintype "passive"))
    )
    (net (code "179") (name "WRITE(0)") (class "Default")
      (node (ref "IC1") (pin "27") (pinfunction "~{WE}_27") (pintype "input"))
      (node (ref "IC10") (pin "6") (pinfunction "~{Q}_6") (pintype "output"))
      (node (ref "IC4") (pin "1") (pinfunction "G_1") (pintype "input"))
      (node (ref "IC4") (pin "19") (pinfunction "G_19") (pintype "input"))
      (node (ref "SV2") (pin "3") (pinfunction "3_3") (pintype "passive"))
      (node (ref "SV4") (pin "3") (pinfunction "3_3") (pintype "passive"))
    )
    (net (code "180") (name "unconnected-(IC2-I{slash}O5-Pad17)") (class "Default")
      (node (ref "IC2") (pin "17") (pinfunction "I/O5_17") (pintype "bidirectional"))
    )
    (net (code "181") (name "unconnected-(IC2-I{slash}O6-Pad18)") (class "Default")
      (node (ref "IC2") (pin "18") (pinfunction "I/O6_18") (pintype "bidirectional"))
    )
    (net (code "182") (name "unconnected-(IC2-I{slash}O7-Pad19)") (class "Default")
      (node (ref "IC2") (pin "19") (pinfunction "I/O7_19") (pintype "bidirectional"))
    )
    (net (code "183") (name "unconnected-(IC7B-Y2-Pad7)") (class "Default")
      (node (ref "IC7") (pin "7") (pinfunction "Y2_7") (pintype "tri_state"))
    )
    (net (code "184") (name "unconnected-(IC7B-Y3-Pad5)") (class "Default")
      (node (ref "IC7") (pin "5") (pinfunction "Y3_5") (pintype "tri_state"))
    )
    (net (code "185") (name "unconnected-(IC7B-Y4-Pad3)") (class "Default")
      (node (ref "IC7") (pin "3") (pinfunction "Y4_3") (pintype "tri_state"))
    )
    (net (code "186") (name "unconnected-(IC10B-~{Q}-Pad8)") (class "Default")
      (node (ref "IC10") (pin "8") (pinfunction "~{Q}_8") (pintype "output"))
    )
  )
)
